# LPC4357_SDRAM.net
KiCad netlist of a schematic drawn in Altium Designer
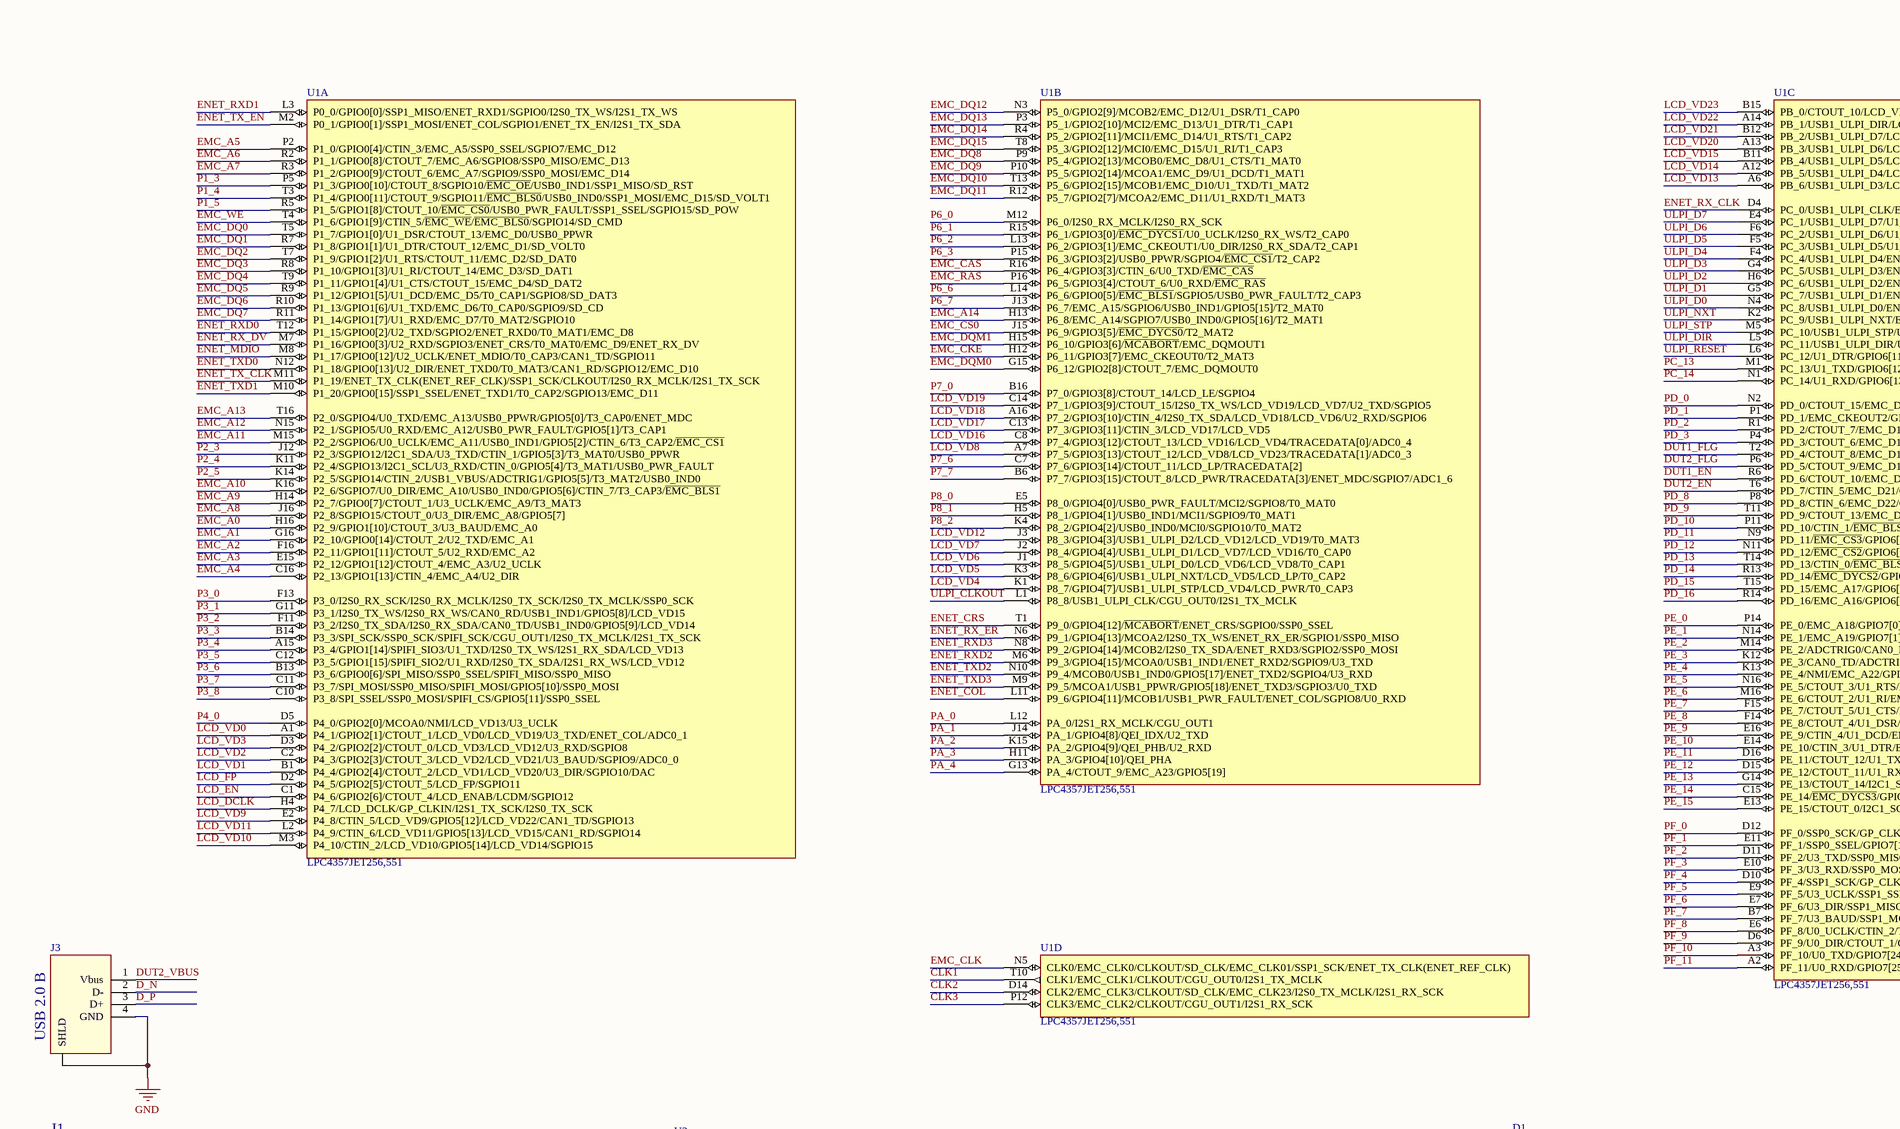
[diagram p0: LPC4357_SDRAM.SchDoc, top left]
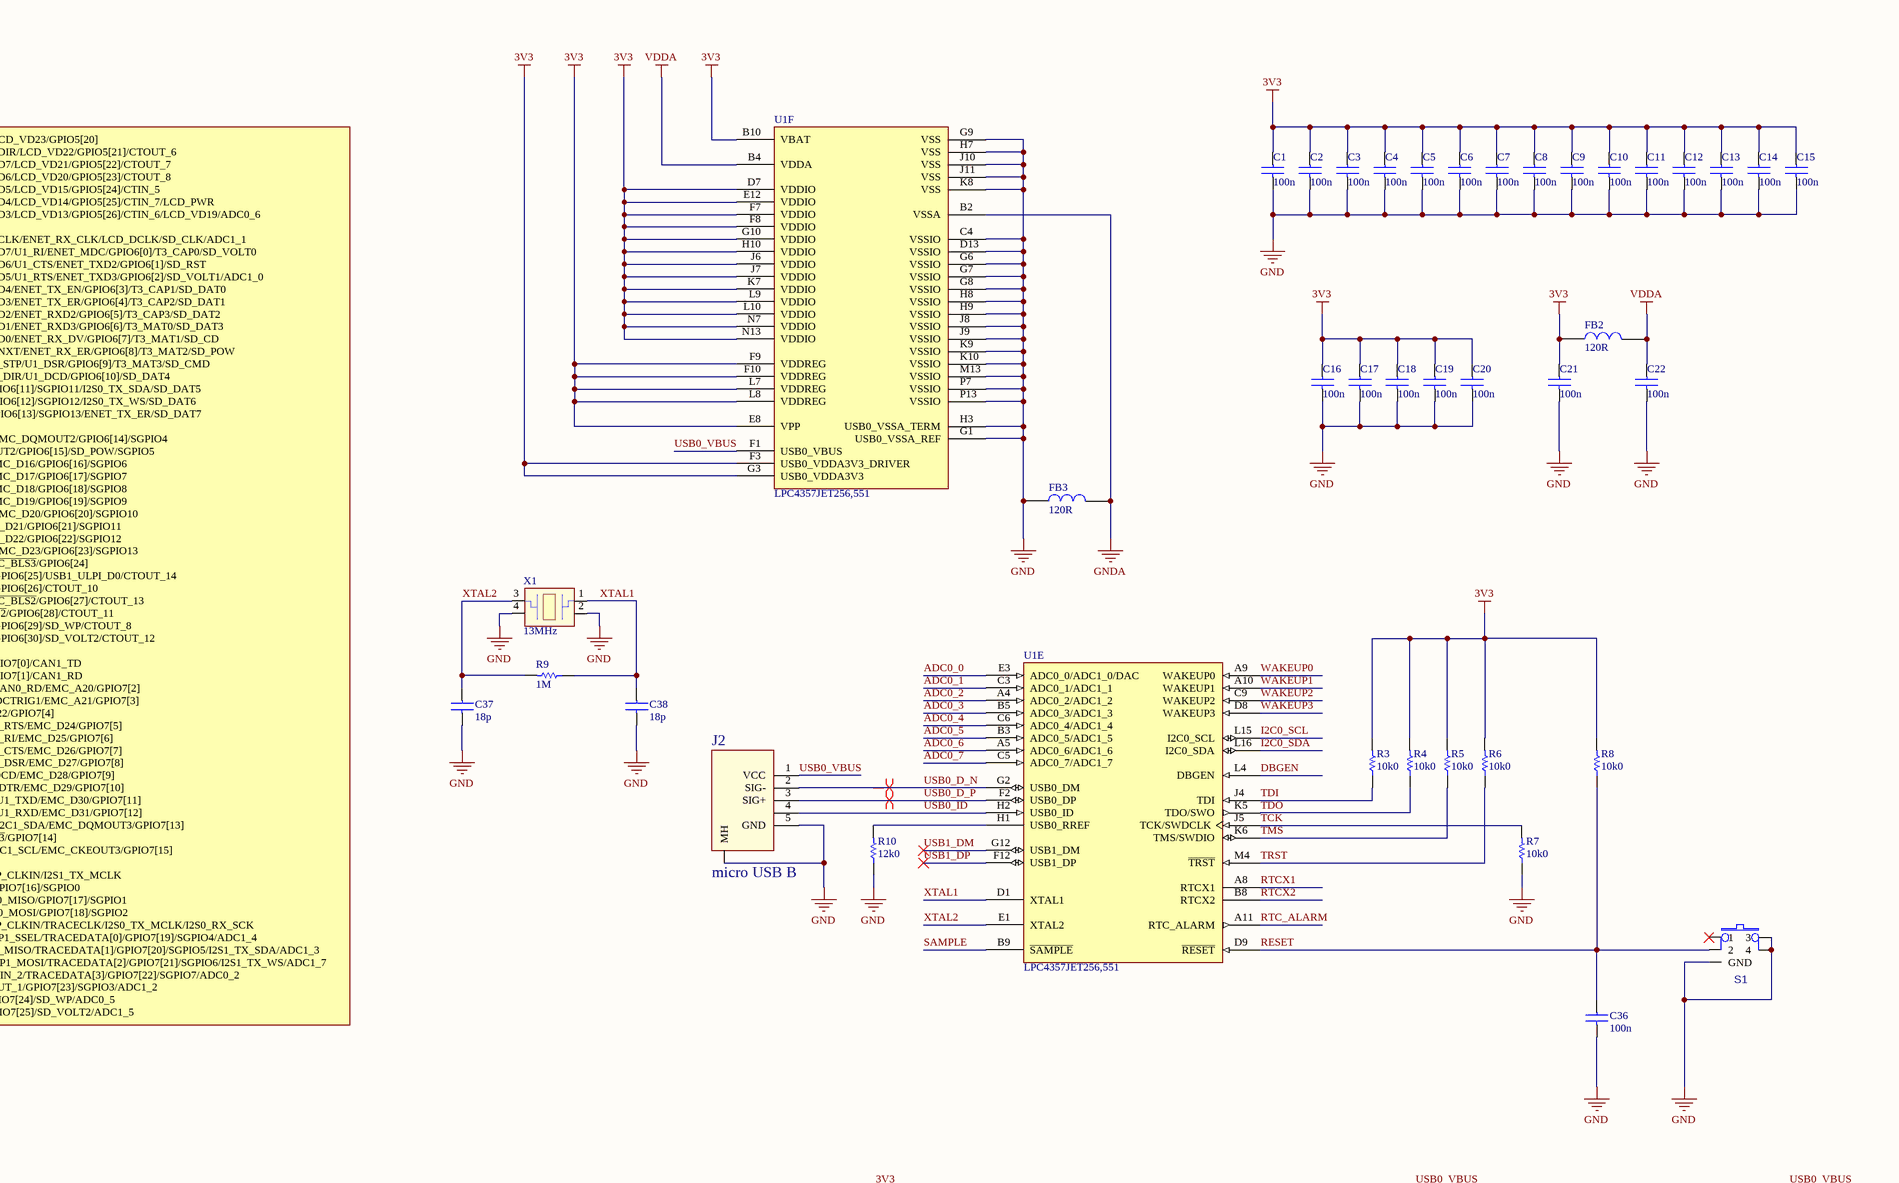
[diagram p1: LPC4357_SDRAM.SchDoc, top right]
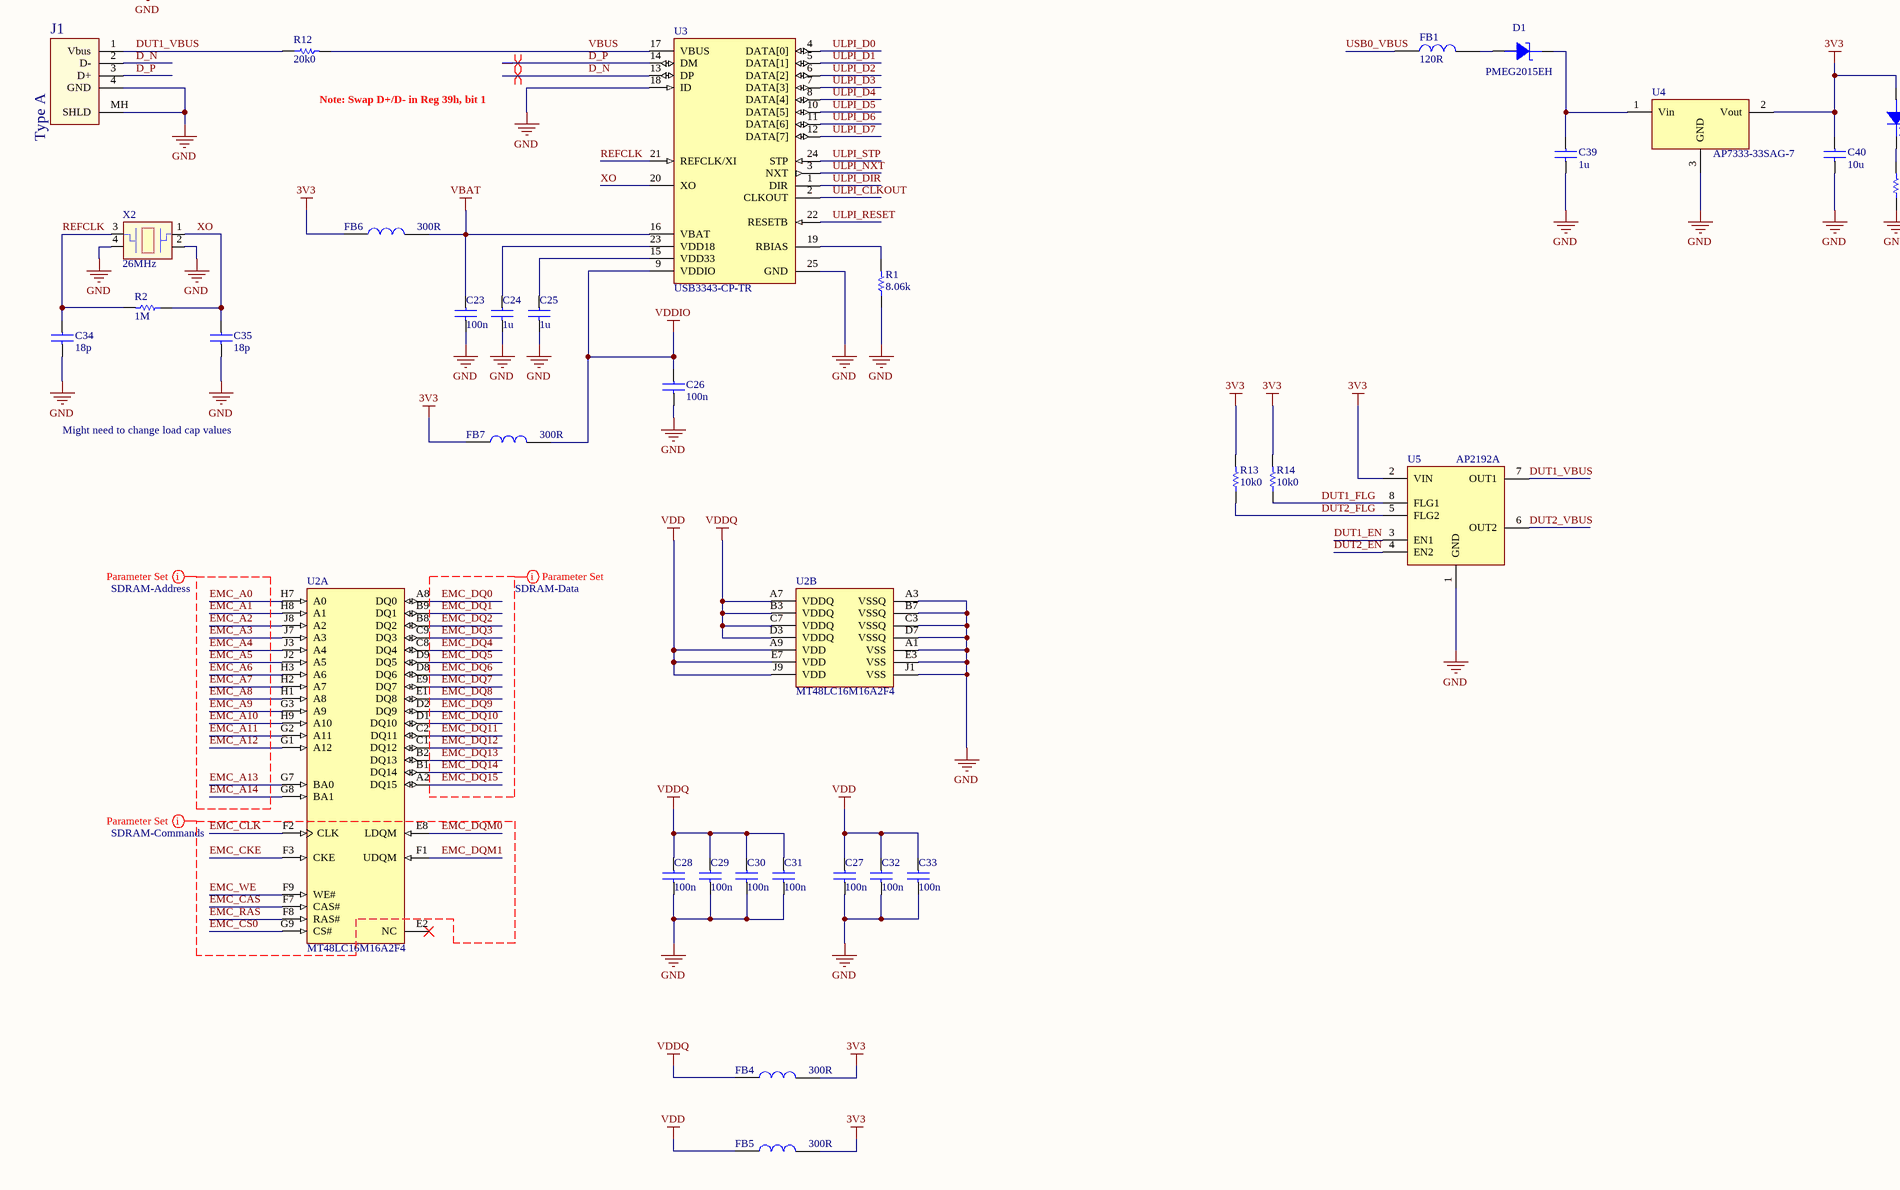
[diagram p2: LPC4357_SDRAM.SchDoc, bottom left]
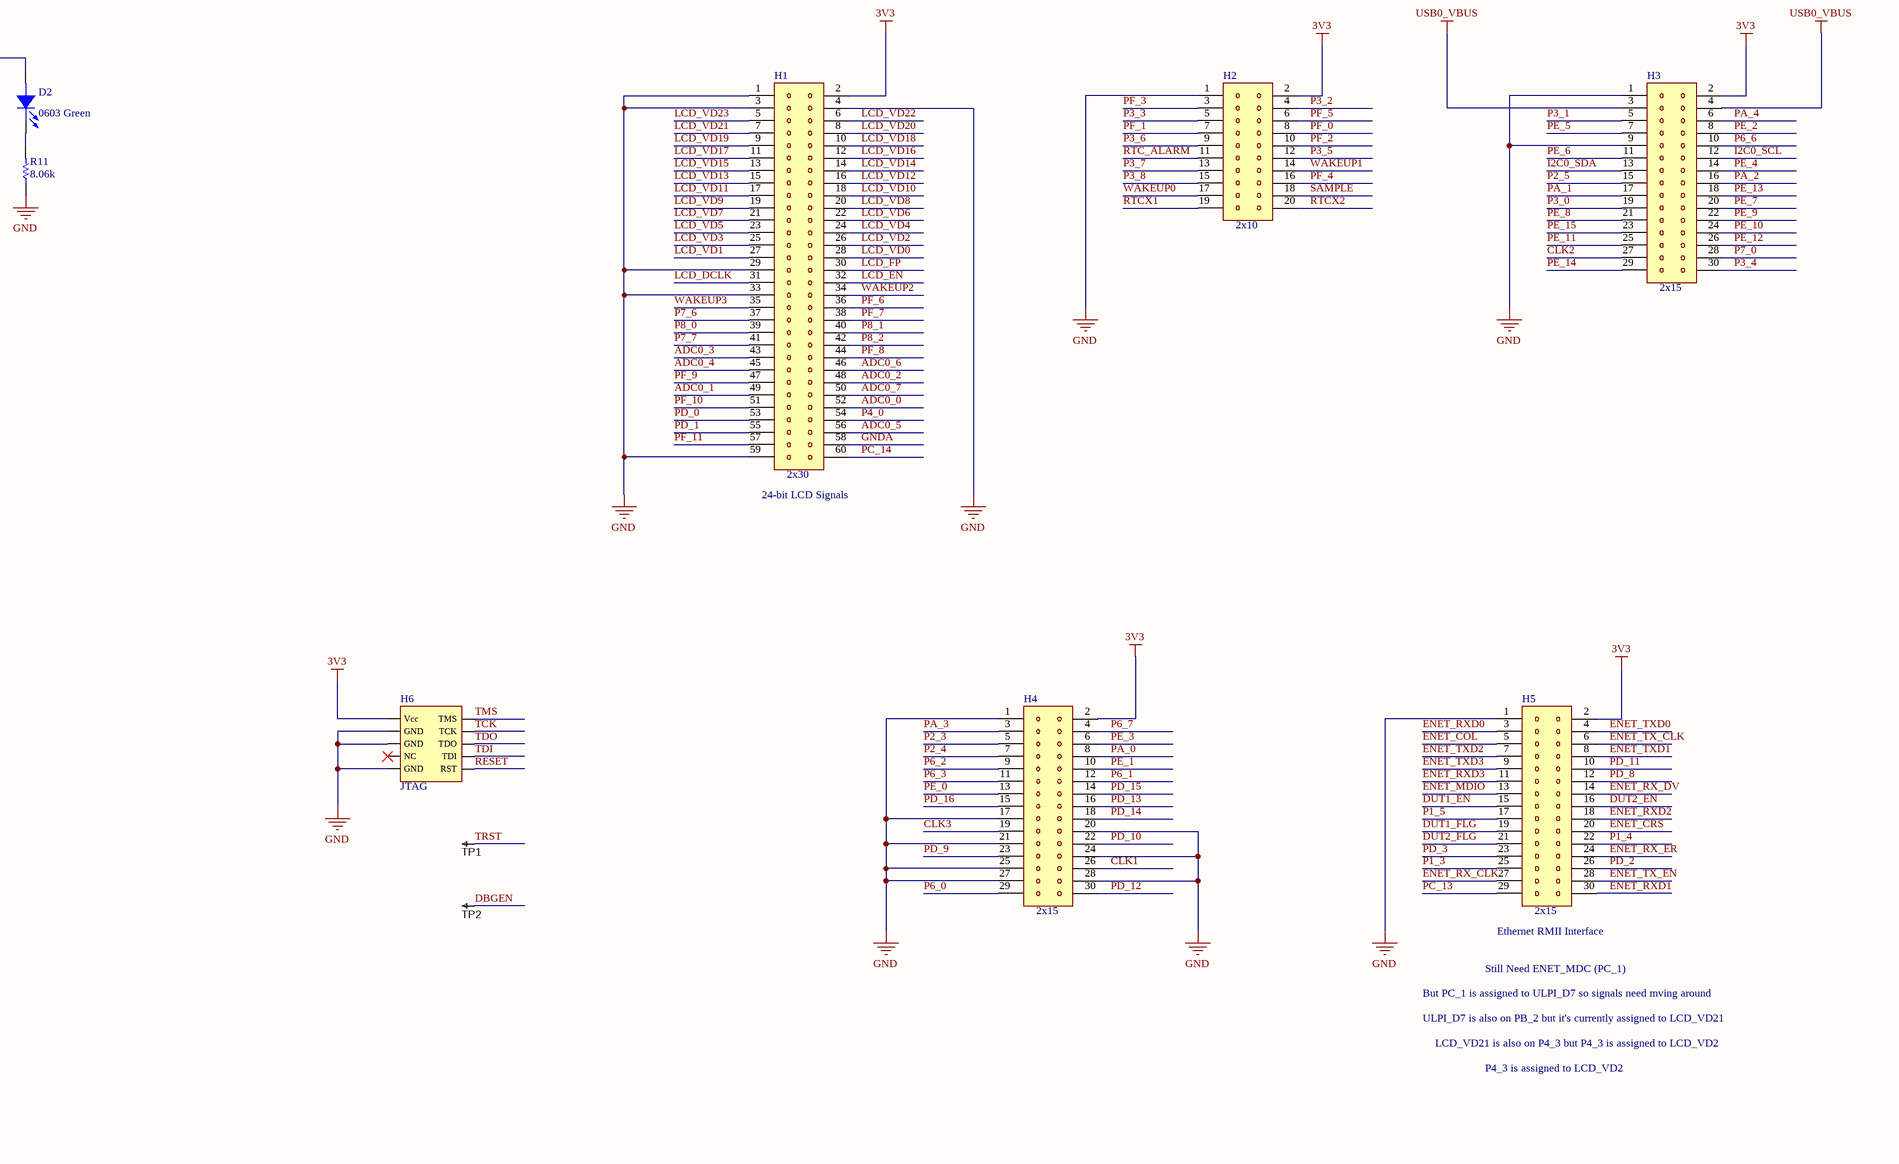
[diagram p3: LPC4357_SDRAM.SchDoc, bottom right]

(export (version "E")
  (design (tool "Eeschema 10.0.6"))
  (components
    (comp (ref "C1")
      (value "100n")
      (footprint "C_0402_N")
      (description "Cap, Chip, 100nF, 16V, +/-10%, X7R, 0402")
      (fields (field (name "MANUFACTURER") "NIC"))
      (libsource (lib "GLIB") (part "C_100n_16V_10_0402_NIC"))
    )
    (comp (ref "C2")
      (value "100n")
      (footprint "C_0402_N")
      (description "Cap, Chip, 100nF, 16V, +/-10%, X7R, 0402")
      (fields (field (name "MANUFACTURER") "NIC"))
      (libsource (lib "GLIB") (part "C_100n_16V_10_0402_NIC"))
    )
    (comp (ref "C3")
      (value "100n")
      (footprint "C_0402_N")
      (description "Cap, Chip, 100nF, 16V, +/-10%, X7R, 0402")
      (fields (field (name "MANUFACTURER") "NIC"))
      (libsource (lib "GLIB") (part "C_100n_16V_10_0402_NIC"))
    )
    (comp (ref "C4")
      (value "100n")
      (footprint "C_0402_N")
      (description "Cap, Chip, 100nF, 16V, +/-10%, X7R, 0402")
      (fields (field (name "MANUFACTURER") "NIC"))
      (libsource (lib "GLIB") (part "C_100n_16V_10_0402_NIC"))
    )
    (comp (ref "C5")
      (value "100n")
      (footprint "C_0402_N")
      (description "Cap, Chip, 100nF, 16V, +/-10%, X7R, 0402")
      (fields (field (name "MANUFACTURER") "NIC"))
      (libsource (lib "GLIB") (part "C_100n_16V_10_0402_NIC"))
    )
    (comp (ref "C6")
      (value "100n")
      (footprint "C_0402_N")
      (description "Cap, Chip, 100nF, 16V, +/-10%, X7R, 0402")
      (fields (field (name "MANUFACTURER") "NIC"))
      (libsource (lib "GLIB") (part "C_100n_16V_10_0402_NIC"))
    )
    (comp (ref "C7")
      (value "100n")
      (footprint "C_0402_N")
      (description "Cap, Chip, 100nF, 16V, +/-10%, X7R, 0402")
      (fields (field (name "MANUFACTURER") "NIC"))
      (libsource (lib "GLIB") (part "C_100n_16V_10_0402_NIC"))
    )
    (comp (ref "C8")
      (value "100n")
      (footprint "C_0402_N")
      (description "Cap, Chip, 100nF, 16V, +/-10%, X7R, 0402")
      (fields (field (name "MANUFACTURER") "NIC"))
      (libsource (lib "GLIB") (part "C_100n_16V_10_0402_NIC"))
    )
    (comp (ref "C9")
      (value "100n")
      (footprint "C_0402_N")
      (description "Cap, Chip, 100nF, 16V, +/-10%, X7R, 0402")
      (fields (field (name "MANUFACTURER") "NIC"))
      (libsource (lib "GLIB") (part "C_100n_16V_10_0402_NIC"))
    )
    (comp (ref "C10")
      (value "100n")
      (footprint "C_0402_N")
      (description "Cap, Chip, 100nF, 16V, +/-10%, X7R, 0402")
      (fields (field (name "MANUFACTURER") "NIC"))
      (libsource (lib "GLIB") (part "C_100n_16V_10_0402_NIC"))
    )
    (comp (ref "C11")
      (value "100n")
      (footprint "C_0402_N")
      (description "Cap, Chip, 100nF, 16V, +/-10%, X7R, 0402")
      (fields (field (name "MANUFACTURER") "NIC"))
      (libsource (lib "GLIB") (part "C_100n_16V_10_0402_NIC"))
    )
    (comp (ref "C12")
      (value "100n")
      (footprint "C_0402_N")
      (description "Cap, Chip, 100nF, 16V, +/-10%, X7R, 0402")
      (fields (field (name "MANUFACTURER") "NIC"))
      (libsource (lib "GLIB") (part "C_100n_16V_10_0402_NIC"))
    )
    (comp (ref "C13")
      (value "100n")
      (footprint "C_0402_N")
      (description "Cap, Chip, 100nF, 16V, +/-10%, X7R, 0402")
      (fields (field (name "MANUFACTURER") "NIC"))
      (libsource (lib "GLIB") (part "C_100n_16V_10_0402_NIC"))
    )
    (comp (ref "C14")
      (value "100n")
      (footprint "C_0402_N")
      (description "Cap, Chip, 100nF, 16V, +/-10%, X7R, 0402")
      (fields (field (name "MANUFACTURER") "NIC"))
      (libsource (lib "GLIB") (part "C_100n_16V_10_0402_NIC"))
    )
    (comp (ref "C15")
      (value "100n")
      (footprint "C_0402_N")
      (description "Cap, Chip, 100nF, 16V, +/-10%, X7R, 0402")
      (fields (field (name "MANUFACTURER") "NIC"))
      (libsource (lib "GLIB") (part "C_100n_16V_10_0402_NIC"))
    )
    (comp (ref "C16")
      (value "100n")
      (footprint "C_0402_N")
      (description "Cap, Chip, 100nF, 16V, +/-10%, X7R, 0402")
      (fields (field (name "MANUFACTURER") "NIC"))
      (libsource (lib "GLIB") (part "C_100n_16V_10_0402_NIC"))
    )
    (comp (ref "C17")
      (value "100n")
      (footprint "C_0402_N")
      (description "Cap, Chip, 100nF, 16V, +/-10%, X7R, 0402")
      (fields (field (name "MANUFACTURER") "NIC"))
      (libsource (lib "GLIB") (part "C_100n_16V_10_0402_NIC"))
    )
    (comp (ref "C18")
      (value "100n")
      (footprint "C_0402_N")
      (description "Cap, Chip, 100nF, 16V, +/-10%, X7R, 0402")
      (fields (field (name "MANUFACTURER") "NIC"))
      (libsource (lib "GLIB") (part "C_100n_16V_10_0402_NIC"))
    )
    (comp (ref "C19")
      (value "100n")
      (footprint "C_0402_N")
      (description "Cap, Chip, 100nF, 16V, +/-10%, X7R, 0402")
      (fields (field (name "MANUFACTURER") "NIC"))
      (libsource (lib "GLIB") (part "C_100n_16V_10_0402_NIC"))
    )
    (comp (ref "C20")
      (value "100n")
      (footprint "C_0402_N")
      (description "Cap, Chip, 100nF, 16V, +/-10%, X7R, 0402")
      (fields (field (name "MANUFACTURER") "NIC"))
      (libsource (lib "GLIB") (part "C_100n_16V_10_0402_NIC"))
    )
    (comp (ref "C21")
      (value "100n")
      (footprint "C_0402_N")
      (description "Cap, Chip, 100nF, 16V, +/-10%, X7R, 0402")
      (fields (field (name "MANUFACTURER") "NIC"))
      (libsource (lib "GLIB") (part "C_100n_16V_10_0402_NIC"))
    )
    (comp (ref "C22")
      (value "100n")
      (footprint "C_0402_N")
      (description "Cap, Chip, 100nF, 16V, +/-10%, X7R, 0402")
      (fields (field (name "MANUFACTURER") "NIC"))
      (libsource (lib "GLIB") (part "C_100n_16V_10_0402_NIC"))
    )
    (comp (ref "C23")
      (value "100n")
      (footprint "C_0402_N")
      (description "Cap, Chip, 100nF, 16V, +/-10%, X7R, 0402")
      (fields (field (name "MANUFACTURER") "NIC"))
      (libsource (lib "GLIB") (part "C_100n_16V_10_0402_NIC"))
    )
    (comp (ref "C24")
      (value "1u")
      (footprint "C_0402_N")
      (description "Cap, Chip, 1uF, 10V, 10%, X5R, 0402")
      (fields (field (name "MANUFACTURER") "NIC"))
      (libsource (lib "GLIB") (part "C_1u_10V_10_0402_NIC"))
    )
    (comp (ref "C25")
      (value "1u")
      (footprint "C_0402_N")
      (description "Cap, Chip, 1uF, 10V, 10%, X5R, 0402")
      (fields (field (name "MANUFACTURER") "NIC"))
      (libsource (lib "GLIB") (part "C_1u_10V_10_0402_NIC"))
    )
    (comp (ref "C26")
      (value "100n")
      (footprint "C_0402_N")
      (description "Cap, Chip, 100nF, 16V, +/-10%, X7R, 0402")
      (fields (field (name "MANUFACTURER") "NIC"))
      (libsource (lib "GLIB") (part "C_100n_16V_10_0402_NIC"))
    )
    (comp (ref "C27")
      (value "100n")
      (footprint "C_0402_N")
      (description "Cap, Chip, 100nF, 16V, +/-10%, X7R, 0402")
      (fields (field (name "MANUFACTURER") "NIC"))
      (libsource (lib "GLIB") (part "C_100n_16V_10_0402_NIC"))
    )
    (comp (ref "C28")
      (value "100n")
      (footprint "C_0402_N")
      (description "Cap, Chip, 100nF, 16V, +/-10%, X7R, 0402")
      (fields (field (name "MANUFACTURER") "NIC"))
      (libsource (lib "GLIB") (part "C_100n_16V_10_0402_NIC"))
    )
    (comp (ref "C29")
      (value "100n")
      (footprint "C_0402_N")
      (description "Cap, Chip, 100nF, 16V, +/-10%, X7R, 0402")
      (fields (field (name "MANUFACTURER") "NIC"))
      (libsource (lib "GLIB") (part "C_100n_16V_10_0402_NIC"))
    )
    (comp (ref "C30")
      (value "100n")
      (footprint "C_0402_N")
      (description "Cap, Chip, 100nF, 16V, +/-10%, X7R, 0402")
      (fields (field (name "MANUFACTURER") "NIC"))
      (libsource (lib "GLIB") (part "C_100n_16V_10_0402_NIC"))
    )
    (comp (ref "C31")
      (value "100n")
      (footprint "C_0402_N")
      (description "Cap, Chip, 100nF, 16V, +/-10%, X7R, 0402")
      (fields (field (name "MANUFACTURER") "NIC"))
      (libsource (lib "GLIB") (part "C_100n_16V_10_0402_NIC"))
    )
    (comp (ref "C32")
      (value "100n")
      (footprint "C_0402_N")
      (description "Cap, Chip, 100nF, 16V, +/-10%, X7R, 0402")
      (fields (field (name "MANUFACTURER") "NIC"))
      (libsource (lib "GLIB") (part "C_100n_16V_10_0402_NIC"))
    )
    (comp (ref "C33")
      (value "100n")
      (footprint "C_0402_N")
      (description "Cap, Chip, 100nF, 16V, +/-10%, X7R, 0402")
      (fields (field (name "MANUFACTURER") "NIC"))
      (libsource (lib "GLIB") (part "C_100n_16V_10_0402_NIC"))
    )
    (comp (ref "C34")
      (value "18p")
      (footprint "C_0402_N")
      (description "Cap, Chip, 18pF, 25V, 10%, NPO 0402")
      (fields (field (name "MANUFACTURER") "NIC"))
      (libsource (lib "GLIB") (part "C_18p_25V_10_0402_NIC"))
    )
    (comp (ref "C35")
      (value "18p")
      (footprint "C_0402_N")
      (description "Cap, Chip, 18pF, 25V, 10%, NPO 0402")
      (fields (field (name "MANUFACTURER") "NIC"))
      (libsource (lib "GLIB") (part "C_18p_25V_10_0402_NIC"))
    )
    (comp (ref "C36")
      (value "100n")
      (footprint "C_0402_N")
      (description "Cap, Chip, 100nF, 16V, +/-10%, X7R, 0402")
      (fields (field (name "MANUFACTURER") "NIC"))
      (libsource (lib "GLIB") (part "C_100n_16V_10_0402_NIC"))
    )
    (comp (ref "C37")
      (value "18p")
      (footprint "C_0402_N")
      (description "Cap, Chip, 18pF, 25V, 10%, NPO 0402")
      (fields (field (name "MANUFACTURER") "NIC"))
      (libsource (lib "GLIB") (part "C_18p_25V_10_0402_NIC"))
    )
    (comp (ref "C38")
      (value "18p")
      (footprint "C_0402_N")
      (description "Cap, Chip, 18pF, 25V, 10%, NPO 0402")
      (fields (field (name "MANUFACTURER") "NIC"))
      (libsource (lib "GLIB") (part "C_18p_25V_10_0402_NIC"))
    )
    (comp (ref "C39")
      (value "1u")
      (footprint "C_0402_N")
      (description "Cap, Chip, 1uF, 10V, 10%, X5R, 0402")
      (fields (field (name "MANUFACTURER") "NIC"))
      (libsource (lib "GLIB") (part "C_1u_10V_10_0402_NIC"))
    )
    (comp (ref "C40")
      (value "10u")
      (footprint "0603x55")
      (description "Cap, Chip, 10uF, 10V, ± 15%, X5R, 0603")
      (fields (field (name "MANUFACTURER") "NIC"))
      (libsource (lib "GLIB") (part "C_10u_10V_10_0603_NIC"))
    )
    (comp (ref "D1")
      (value "PMEG2015EH")
      (footprint "SOD123F")
      (description "Diode, Schottky Rectifier, 20V, 1.5A, SOT123F")
      (fields (field (name "VOLTAGE") "20V") (field (name "MANUFACTURER") "NXP Semiconductors"))
      (libsource (lib "GLIB") (part "D_PMEG2015EH_20V_1A5_SOT123F"))
    )
    (comp (ref "D2")
      (value "0603 Green")
      (footprint "D_0603")
      (description "0603 LED, Green")
      (fields (field (name "MANUFACTURER") "Lite-on"))
      (libsource (lib "GLIB") (part "D_LED-0603_LTST-C190KGKT"))
    )
    (comp (ref "FB1")
      (value "120R")
      (footprint "L_0603")
      (description "Ferrite bead,120 ohm@100MHz,0.30 ohm @DC, 500mA, 0603")
      (fields (field (name "MANUFACTURER") "NIC"))
      (libsource (lib "GLIB") (part "FB_120R_0603_NIC"))
    )
    (comp (ref "FB2")
      (value "120R")
      (footprint "L_0603")
      (description "Ferrite bead,120 ohm@100MHz,0.30 ohm @DC, 500mA, 0603")
      (fields (field (name "MANUFACTURER") "NIC"))
      (libsource (lib "GLIB") (part "FB_120R_0603_NIC"))
    )
    (comp (ref "FB3")
      (value "120R")
      (footprint "L_0603")
      (description "Ferrite bead,120 ohm@100MHz,0.30 ohm @DC, 500mA, 0603")
      (fields (field (name "MANUFACTURER") "NIC"))
      (libsource (lib "GLIB") (part "FB_120R_0603_NIC"))
    )
    (comp (ref "FB4")
      (value "300R")
      (footprint "FB_0402-NIC")
      (description "Ferrite bead,300 ohm@100MHz,0.15 ohm @DC, 1A, 0402")
      (fields (field (name "MANUFACTURER") "NIC"))
      (libsource (lib "GLIB") (part "FB_300R_0402_NIC"))
    )
    (comp (ref "FB5")
      (value "300R")
      (footprint "FB_0402-NIC")
      (description "Ferrite bead,300 ohm@100MHz,0.15 ohm @DC, 1A, 0402")
      (fields (field (name "MANUFACTURER") "NIC"))
      (libsource (lib "GLIB") (part "FB_300R_0402_NIC"))
    )
    (comp (ref "FB6")
      (value "300R")
      (footprint "FB_0402-NIC")
      (description "Ferrite bead,300 ohm@100MHz,0.15 ohm @DC, 1A, 0402")
      (fields (field (name "MANUFACTURER") "NIC"))
      (libsource (lib "GLIB") (part "FB_300R_0402_NIC"))
    )
    (comp (ref "FB7")
      (value "300R")
      (footprint "FB_0402-NIC")
      (description "Ferrite bead,300 ohm@100MHz,0.15 ohm @DC, 1A, 0402")
      (fields (field (name "MANUFACTURER") "NIC"))
      (libsource (lib "GLIB") (part "FB_300R_0402_NIC"))
    )
    (comp (ref "H1")
      (value "2x30")
      (footprint "HDR_2x30_1.27mm")
      (description "CONN, Header, 2x30, TH, 1.27mm")
      (fields (field (name "MANUFACTURER") "Shenzhen Cankemeng"))
      (libsource (lib "GLIB") (part "JP_2x30_1.27mm"))
    )
    (comp (ref "H2")
      (value "2x10")
      (footprint "HDR_2x10_1.27mm")
      (description "CONN, Header, 2x10, TH, 1.27mm")
      (libsource (lib "GLIB") (part "JP_2x10_1.27mm"))
    )
    (comp (ref "H3")
      (value "2x15")
      (footprint "HDR_2x15_1.27mm")
      (description "CONN, Header, 2x15, TH, 1.27mm")
      (libsource (lib "GLIB") (part "JP_2x15_1.27mm"))
    )
    (comp (ref "H4")
      (value "2x15")
      (footprint "HDR_2x15_1.27mm")
      (description "CONN, Header, 2x15, TH, 1.27mm")
      (libsource (lib "GLIB") (part "JP_2x15_1.27mm"))
    )
    (comp (ref "H5")
      (value "2x15")
      (footprint "HDR_2x15_1.27mm")
      (description "CONN, Header, 2x15, TH, 1.27mm")
      (libsource (lib "GLIB") (part "JP_2x15_1.27mm"))
    )
    (comp (ref "H6")
      (value "JTAG")
      (footprint "JTAG_FTSH-105-01-XXX-D-K")
      (description "CONN, Header 2x5, TH, 1.27mm")
      (fields (field (name "MANUFACTURER") "Samtec"))
      (libsource (lib "GLIB") (part "JP_JTAG-FTSH_1.27"))
    )
    (comp (ref "J1")
      (value "Type A")
      (footprint "USB_A_F_SIDE_REVERSE_TH")
      (description "USB, Type A, Side Insert, Revese PinoutRA")
      (fields (field (name "MANUFACTURER") "Jing Extension"))
      (libsource (lib "GLIB") (part "J_USB_A_Rotate_Reverse_TH"))
    )
    (comp (ref "J2")
      (value "micro USB B")
      (footprint "10118194")
      (description "CONN RECEPT MICRO USB RA 5POS SMD")
      (fields (field (name "MANUFACTURER") "FCI"))
      (libsource (lib "GLIB") (part "J_microUSB_B_SMD-FCI"))
    )
    (comp (ref "J3")
      (value "USB 2.0 B")
      (footprint "USB_B_F_RA_TH")
      (description "CONN RCPT USB 2.0 TYPE B R/A 4PS")
      (fields (field (name "MANUFACTURER") "FCI"))
      (libsource (lib "GLIB") (part "J_USB_B_2.0_RA"))
    )
    (comp (ref "R1")
      (value "8.06k")
      (footprint "R_0402-N")
      (description "Resistor 8.06 kOhm, 1%, 0.1W, 0402")
      (libsource (lib "GLIB") (part "Res Semi"))
    )
    (comp (ref "R2")
      (value "1M")
      (footprint "R_0402-N")
      (description "Semiconductor Resistor")
      (libsource (lib "GLIB") (part "Res Semi"))
    )
    (comp (ref "R3")
      (value "10k0")
      (footprint "R_0402-N")
      (description "Resistor, 10.0 kΩ, 1%, 0.06W, 0402")
      (fields (field (name "MANUFACTURER") "NIC"))
      (libsource (lib "GLIB") (part "R_10k0_60mW_1_0402_NIC"))
    )
    (comp (ref "R4")
      (value "10k0")
      (footprint "R_0402-N")
      (description "Resistor, 10.0 kΩ, 1%, 0.06W, 0402")
      (fields (field (name "MANUFACTURER") "NIC"))
      (libsource (lib "GLIB") (part "R_10k0_60mW_1_0402_NIC"))
    )
    (comp (ref "R5")
      (value "10k0")
      (footprint "R_0402-N")
      (description "Resistor, 10.0 kΩ, 1%, 0.06W, 0402")
      (fields (field (name "MANUFACTURER") "NIC"))
      (libsource (lib "GLIB") (part "R_10k0_60mW_1_0402_NIC"))
    )
    (comp (ref "R6")
      (value "10k0")
      (footprint "R_0402-N")
      (description "Resistor, 10.0 kΩ, 1%, 0.06W, 0402")
      (fields (field (name "MANUFACTURER") "NIC"))
      (libsource (lib "GLIB") (part "R_10k0_60mW_1_0402_NIC"))
    )
    (comp (ref "R7")
      (value "10k0")
      (footprint "R_0402-N")
      (description "Resistor, 10.0 kΩ, 1%, 0.06W, 0402")
      (fields (field (name "MANUFACTURER") "NIC"))
      (libsource (lib "GLIB") (part "R_10k0_60mW_1_0402_NIC"))
    )
    (comp (ref "R8")
      (value "10k0")
      (footprint "R_0402-N")
      (description "Resistor, 10.0 kΩ, 1%, 0.06W, 0402")
      (fields (field (name "MANUFACTURER") "NIC"))
      (libsource (lib "GLIB") (part "R_10k0_60mW_1_0402_NIC"))
    )
    (comp (ref "R9")
      (value "1M")
      (footprint "R_0402-N")
      (description "Semiconductor Resistor")
      (libsource (lib "GLIB") (part "Res Semi"))
    )
    (comp (ref "R10")
      (value "12k0")
      (footprint "R_0402-N")
      (description "Resistor 12.0 kΩ, 1%, 0.06W, 0402")
      (fields (field (name "MANUFACTURER") "NIC"))
      (libsource (lib "GLIB") (part "R_12k0_60mW_1_0402_NIC"))
    )
    (comp (ref "R11")
      (value "8.06k")
      (footprint "R_0402-N")
      (description "Resistor 8.06 kOhm, 1%, 0.1W, 0402")
      (libsource (lib "GLIB") (part "Res Semi"))
    )
    (comp (ref "R12")
      (value "20k0")
      (footprint "R_0402-N")
      (description "Resistor 20 kOhm, 1%, 0.1W, 0603")
      (fields (field (name "MANUFACTURER") "NIC"))
      (libsource (lib "GLIB") (part "R_20k0_100mW_1_0603_NIC"))
    )
    (comp (ref "R13")
      (value "10k0")
      (footprint "R_0402-N")
      (description "Resistor, 10.0 kΩ, 1%, 0.06W, 0402")
      (fields (field (name "MANUFACTURER") "NIC"))
      (libsource (lib "GLIB") (part "R_10k0_60mW_1_0402_NIC"))
    )
    (comp (ref "R14")
      (value "10k0")
      (footprint "R_0402-N")
      (description "Resistor, 10.0 kΩ, 1%, 0.06W, 0402")
      (fields (field (name "MANUFACTURER") "NIC"))
      (libsource (lib "GLIB") (part "R_10k0_60mW_1_0402_NIC"))
    )
    (comp (ref "S1")
      (value "PTS840")
      (footprint "SW_PTS840")
      (description "SWITCH SPST RA, 50mA, 24V, SMT")
      (fields (field (name "MANUFACTURER") "C&K"))
      (libsource (lib "GLIB") (part "SW_PTS840_RA_SMT"))
    )
    (comp (ref "TP1")
      (value "TP_60mil-pad")
      (footprint "TP-R50")
      (description "SMD test pin")
      (libsource (lib "GLIB") (part "TP_50mil-pad"))
    )
    (comp (ref "TP2")
      (value "TP_60mil-pad")
      (footprint "TP-R50")
      (description "SMD test pin")
      (libsource (lib "GLIB") (part "TP_50mil-pad"))
    )
    (comp (ref "U1")
      (value "LPC4357JET256,551")
      (footprint "NXP-SOT740-2")
      (fields (field (name "MANUFACTURER") "NXP Semiconductors") (field (name "PARTNUMBER") "LPC4357JET256"))
      (libsource (lib "GLIB") (part "U_LPC4357JET256_BGA256"))
    )
    (comp (ref "U2")
      (value "MT48LC16M16A2F4")
      (footprint "VFBGA54_8x8")
      (description "256Mb PC133 SDR SDRAM, 16Mb x 16, 7.5ns, 3.3V, 0 to 70 degC, 54-Ball VFBGA, Pb-Free")
      (fields (field (name "PARTNUMBER") "MT48LC16M16A2BG-75") (field (name "VOLTAGE") "3.3V"))
      (libsource (lib "GLIB") (part "U_MT48LC16M16A2F4_VFBGA54"))
    )
    (comp (ref "U3")
      (value "USB3343-CP-TR")
      (footprint "MCHP-QFN-24_A_V")
      (fields (field (name "MANUFACTURER") "Microchip"))
      (libsource (lib "GLIB") (part "U_USB3343_QFN24"))
    )
    (comp (ref "U4")
      (value "AP7333-33SAG-7")
      (footprint "SOT23_N")
      (description "IC, CONV DC/DC LDO 3.3V, 300mA, SOT23-3")
      (fields (field (name "MANUFACTURER") "STMicroelectronics"))
      (libsource (lib "GLIB") (part "U_AP7333-33SAG-7_SOT23-3"))
    )
    (comp (ref "U5")
      (value "AP2192A")
      (footprint "soic_8")
      (description "IC, USB Dual Switch w/ 1.5A Current Limit, SOIC-8")
      (fields (field (name "MANUFACTURER") "Diodes Inc"))
      (libsource (lib "GLIB") (part "U_AP2192A_SOIC8"))
    )
    (comp (ref "X1")
      (value "13MHz")
      (description "X-tal, 13.000MHz, Cl=20pF, +-18ppm, 3225")
      (fields (field (name "MANUFACTURER") "ABRACON Co"))
      (libsource (lib "GLIB") (part "X_13.000MHZ_18pF_3225"))
    )
    (comp (ref "X2")
      (value "26MHz")
      (description "X-tal, 26.000MHz, Cl=6pF, +-18ppm, 2.0 x 1.6mm")
      (fields (field (name "MANUFACTURER") "muRata"))
      (libsource (lib "GLIB") (part "X_26.000MHZ_6pF_2016"))
    )
  )
  (nets
    (net (code "1") (name "/ADC0_0") (class "Default")
      (node (ref "H1") (pin "52") (pinfunction "52_52") (pintype "passive"))
      (node (ref "U1") (pin "E3") (pinfunction "ADC0_0/ADC1_0/DAC_E3") (pintype "input"))
    )
    (net (code "2") (name "/ADC0_1") (class "Default")
      (node (ref "H1") (pin "49") (pinfunction "49_49") (pintype "passive"))
      (node (ref "U1") (pin "C3") (pinfunction "ADC0_1/ADC1_1_C3") (pintype "input"))
    )
    (net (code "3") (name "/ADC0_2") (class "Default")
      (node (ref "H1") (pin "48") (pinfunction "48_48") (pintype "passive"))
      (node (ref "U1") (pin "A4") (pinfunction "ADC0_2/ADC1_2_A4") (pintype "input"))
    )
    (net (code "4") (name "/ADC0_3") (class "Default")
      (node (ref "H1") (pin "43") (pinfunction "43_43") (pintype "passive"))
      (node (ref "U1") (pin "B5") (pinfunction "ADC0_3/ADC1_3_B5") (pintype "input"))
    )
    (net (code "5") (name "/ADC0_4") (class "Default")
      (node (ref "H1") (pin "45") (pinfunction "45_45") (pintype "passive"))
      (node (ref "U1") (pin "C6") (pinfunction "ADC0_4/ADC1_4_C6") (pintype "input"))
    )
    (net (code "6") (name "/ADC0_5") (class "Default")
      (node (ref "H1") (pin "56") (pinfunction "56_56") (pintype "passive"))
      (node (ref "U1") (pin "B3") (pinfunction "ADC0_5/ADC1_5_B3") (pintype "input"))
    )
    (net (code "7") (name "/ADC0_6") (class "Default")
      (node (ref "H1") (pin "46") (pinfunction "46_46") (pintype "passive"))
      (node (ref "U1") (pin "A5") (pinfunction "ADC0_6/ADC1_6_A5") (pintype "input"))
    )
    (net (code "8") (name "/ADC0_7") (class "Default")
      (node (ref "H1") (pin "50") (pinfunction "50_50") (pintype "passive"))
      (node (ref "U1") (pin "C5") (pinfunction "ADC0_7/ADC1_7_C5") (pintype "input"))
    )
    (net (code "9") (name "/CLK1") (class "Default")
      (node (ref "H4") (pin "26") (pinfunction "26_26") (pintype "passive"))
      (node (ref "U1") (pin "T10") (pinfunction "CLK1/EMC_CLK1/CLKOUT/CGU_OUT0/I2S1_TX_MCLK_T10") (pintype "output"))
    )
    (net (code "10") (name "/CLK2") (class "Default")
      (node (ref "H3") (pin "27") (pinfunction "27_27") (pintype "passive"))
      (node (ref "U1") (pin "D14") (pinfunction "CLK2/EMC_CLK3/CLKOUT/SD_CLK/EMC_CLK23/I2S0_TX_MCLK/I2S1_RX_SCK_D14") (pintype "bidirectional"))
    )
    (net (code "11") (name "/CLK3") (class "Default")
      (node (ref "H4") (pin "19") (pinfunction "19_19") (pintype "passive"))
      (node (ref "U1") (pin "P12") (pinfunction "CLK3/EMC_CLK2/CLKOUT/CGU_OUT1/I2S1_RX_SCK_P12") (pintype "bidirectional"))
    )
    (net (code "12") (name "/DBGEN") (class "Default")
      (node (ref "TP2") (pin "1") (pintype "passive"))
      (node (ref "U1") (pin "L4") (pinfunction "DBGEN_L4") (pintype "input"))
    )
    (net (code "13") (name "/DUT1_EN") (class "Default")
      (node (ref "H5") (pin "15") (pinfunction "15_15") (pintype "passive"))
      (node (ref "U1") (pin "R6") (pinfunction "PD_6/CTOUT_10/EMC_D20/GPIO6[20]/SGPIO10_R6") (pintype "bidirectional"))
      (node (ref "U5") (pin "3") (pinfunction "EN1_3") (pintype "passive"))
    )
    (net (code "14") (name "/DUT1_FLG") (class "Default")
      (node (ref "H5") (pin "19") (pinfunction "19_19") (pintype "passive"))
      (node (ref "R14") (pin "1") (pinfunction "1_1") (pintype "passive"))
      (node (ref "U1") (pin "T2") (pinfunction "PD_4/CTOUT_8/EMC_D18/GPIO6[18]/SGPIO8_T2") (pintype "bidirectional"))
      (node (ref "U5") (pin "8") (pinfunction "FLG1_8") (pintype "passive"))
    )
    (net (code "15") (name "/DUT1_VBUS") (class "Default")
      (node (ref "J1") (pin "1") (pinfunction "Vbus_1") (pintype "power_in"))
      (node (ref "R12") (pin "1") (pinfunction "1_1") (pintype "passive"))
      (node (ref "U5") (pin "7") (pinfunction "OUT1_7") (pintype "power_in"))
    )
    (net (code "16") (name "/DUT2_EN") (class "Default")
      (node (ref "H5") (pin "16") (pinfunction "16_16") (pintype "passive"))
      (node (ref "U1") (pin "T6") (pinfunction "PD_7/CTIN_5/EMC_D21/GPIO6[21]/SGPIO11_T6") (pintype "bidirectional"))
      (node (ref "U5") (pin "4") (pinfunction "EN2_4") (pintype "passive"))
    )
    (net (code "17") (name "/DUT2_FLG") (class "Default")
      (node (ref "H5") (pin "21") (pinfunction "21_21") (pintype "passive"))
      (node (ref "R13") (pin "1") (pinfunction "1_1") (pintype "passive"))
      (node (ref "U1") (pin "P6") (pinfunction "PD_5/CTOUT_9/EMC_D19/GPIO6[19]/SGPIO9_P6") (pintype "bidirectional"))
      (node (ref "U5") (pin "5") (pinfunction "FLG2_5") (pintype "passive"))
    )
    (net (code "18") (name "/DUT2_VBUS") (class "Default")
      (node (ref "J3") (pin "1") (pinfunction "Vbus_1") (pintype "passive"))
      (node (ref "U5") (pin "6") (pinfunction "OUT2_6") (pintype "power_in"))
    )
    (net (code "19") (name "/D_N") (class "Default")
      (node (ref "J1") (pin "2") (pinfunction "D-_2") (pintype "passive"))
      (node (ref "J3") (pin "2") (pinfunction "D-_2") (pintype "passive"))
      (node (ref "U3") (pin "13") (pinfunction "DP_13") (pintype "bidirectional"))
    )
    (net (code "20") (name "/D_P") (class "Default")
      (node (ref "J1") (pin "3") (pinfunction "D+_3") (pintype "passive"))
      (node (ref "J3") (pin "3") (pinfunction "D+_3") (pintype "passive"))
      (node (ref "U3") (pin "14") (pinfunction "DM_14") (pintype "bidirectional"))
    )
    (net (code "21") (name "/EMC_A0") (class "Default")
      (node (ref "U1") (pin "H16") (pinfunction "P2_9/GPIO1[10]/CTOUT_3/U3_BAUD/EMC_A0_H16") (pintype "bidirectional"))
      (node (ref "U2") (pin "H7") (pinfunction "A0_H7") (pintype "input"))
    )
    (net (code "22") (name "/EMC_A1") (class "Default")
      (node (ref "U1") (pin "G16") (pinfunction "P2_10/GPIO0[14]/CTOUT_2/U2_TXD/EMC_A1_G16") (pintype "bidirectional"))
      (node (ref "U2") (pin "H8") (pinfunction "A1_H8") (pintype "input"))
    )
    (net (code "23") (name "/EMC_A2") (class "Default")
      (node (ref "U1") (pin "F16") (pinfunction "P2_11/GPIO1[11]/CTOUT_5/U2_RXD/EMC_A2_F16") (pintype "bidirectional"))
      (node (ref "U2") (pin "J8") (pinfunction "A2_J8") (pintype "input"))
    )
    (net (code "24") (name "/EMC_A3") (class "Default")
      (node (ref "U1") (pin "E15") (pinfunction "P2_12/GPIO1[12]/CTOUT_4/EMC_A3/U2_UCLK_E15") (pintype "bidirectional"))
      (node (ref "U2") (pin "J7") (pinfunction "A3_J7") (pintype "input"))
    )
    (net (code "25") (name "/EMC_A4") (class "Default")
      (node (ref "U1") (pin "C16") (pinfunction "P2_13/GPIO1[13]/CTIN_4/EMC_A4/U2_DIR_C16") (pintype "bidirectional"))
      (node (ref "U2") (pin "J3") (pinfunction "A4_J3") (pintype "input"))
    )
    (net (code "26") (name "/EMC_A5") (class "Default")
      (node (ref "U1") (pin "P2") (pinfunction "P1_0/GPIO0[4]/CTIN_3/EMC_A5/SSP0_SSEL/SGPIO7/EMC_D12_P2") (pintype "bidirectional"))
      (node (ref "U2") (pin "J2") (pinfunction "A5_J2") (pintype "input"))
    )
    (net (code "27") (name "/EMC_A6") (class "Default")
      (node (ref "U1") (pin "R2") (pinfunction "P1_1/GPIO0[8]/CTOUT_7/EMC_A6/SGPIO8/SSP0_MISO/EMC_D13_R2") (pintype "bidirectional"))
      (node (ref "U2") (pin "H3") (pinfunction "A6_H3") (pintype "input"))
    )
    (net (code "28") (name "/EMC_A7") (class "Default")
      (node (ref "U1") (pin "R3") (pinfunction "P1_2/GPIO0[9]/CTOUT_6/EMC_A7/SGPIO9/SSP0_MOSI/EMC_D14_R3") (pintype "bidirectional"))
      (node (ref "U2") (pin "H2") (pinfunction "A7_H2") (pintype "input"))
    )
    (net (code "29") (name "/EMC_A8") (class "Default")
      (node (ref "U1") (pin "J16") (pinfunction "P2_8/SGPIO15/CTOUT_0/U3_DIR/EMC_A8/GPIO5[7]_J16") (pintype "bidirectional"))
      (node (ref "U2") (pin "H1") (pinfunction "A8_H1") (pintype "input"))
    )
    (net (code "30") (name "/EMC_A9") (class "Default")
      (node (ref "U1") (pin "H14") (pinfunction "P2_7/GPIO0[7]/CTOUT_1/U3_UCLK/EMC_A9/T3_MAT3_H14") (pintype "bidirectional"))
      (node (ref "U2") (pin "G3") (pinfunction "A9_G3") (pintype "input"))
    )
    (net (code "31") (name "/EMC_A10") (class "Default")
      (node (ref "U1") (pin "K16") (pinfunction "P2_6/SGPIO7/U0_DIR/EMC_A10/USB0_IND0/GPIO5[6]/CTIN_7/T3_CAP3/~{EMC_BLS1}_K16") (pintype "bidirectional"))
      (node (ref "U2") (pin "H9") (pinfunction "A10_H9") (pintype "input"))
    )
    (net (code "32") (name "/EMC_A11") (class "Default")
      (node (ref "U1") (pin "M15") (pinfunction "P2_2/SGPIO6/U0_UCLK/EMC_A11/USB0_IND1/GPIO5[2]/CTIN_6/T3_CAP2/~{EMC_CS1}_M15") (pintype "bidirectional"))
      (node (ref "U2") (pin "G2") (pinfunction "A11_G2") (pintype "input"))
    )
    (net (code "33") (name "/EMC_A12") (class "Default")
      (node (ref "U1") (pin "N15") (pinfunction "P2_1/SGPIO5/U0_RXD/EMC_A12/USB0_PWR_FAULT/GPIO5[1]/T3_CAP1_N15") (pintype "bidirectional"))
      (node (ref "U2") (pin "G1") (pinfunction "A12_G1") (pintype "input"))
    )
    (net (code "34") (name "/EMC_A13") (class "Default")
      (node (ref "U1") (pin "T16") (pinfunction "P2_0/SGPIO4/U0_TXD/EMC_A13/USB0_PPWR/GPIO5[0]/T3_CAP0/ENET_MDC_T16") (pintype "bidirectional"))
      (node (ref "U2") (pin "G7") (pinfunction "BA0_G7") (pintype "input"))
    )
    (net (code "35") (name "/EMC_A14") (class "Default")
      (node (ref "U1") (pin "H13") (pinfunction "P6_8/EMC_A14/SGPIO7/USB0_IND0/GPIO5[16]/T2_MAT1_H13") (pintype "bidirectional"))
      (node (ref "U2") (pin "G8") (pinfunction "BA1_G8") (pintype "input"))
    )
    (net (code "36") (name "/EMC_CAS") (class "Default")
      (node (ref "U1") (pin "R16") (pinfunction "P6_4/GPIO3[3]/CTIN_6/U0_TXD/~{EMC_CAS}_R16") (pintype "bidirectional"))
      (node (ref "U2") (pin "F7") (pinfunction "CAS#_F7") (pintype "input"))
    )
    (net (code "37") (name "/EMC_CKE") (class "Default")
      (node (ref "U1") (pin "H12") (pinfunction "P6_11/GPIO3[7]/EMC_CKEOUT0/T2_MAT3_H12") (pintype "bidirectional"))
      (node (ref "U2") (pin "F3") (pinfunction "CKE_F3") (pintype "input"))
    )
    (net (code "38") (name "/EMC_CLK") (class "Default")
      (node (ref "U1") (pin "N5") (pinfunction "CLK0/EMC_CLK0/CLKOUT/SD_CLK/EMC_CLK01/SSP1_SCK/ENET_TX_CLK(ENET_REF_CLK)_N5") (pintype "bidirectional"))
      (node (ref "U2") (pin "F2") (pinfunction "CLK_F2") (pintype "input"))
    )
    (net (code "39") (name "/EMC_CS0") (class "Default")
      (node (ref "U1") (pin "J15") (pinfunction "P6_9/GPIO3[5]/~{EMC_DYCS0}/T2_MAT2_J15") (pintype "bidirectional"))
      (node (ref "U2") (pin "G9") (pinfunction "CS#_G9") (pintype "input"))
    )
    (net (code "40") (name "/EMC_DQ0") (class "Default")
      (node (ref "U1") (pin "T5") (pinfunction "P1_7/GPIO1[0]/U1_DSR/CTOUT_13/EMC_D0/USB0_PPWR_T5") (pintype "bidirectional"))
      (node (ref "U2") (pin "A8") (pinfunction "DQ0_A8") (pintype "bidirectional"))
    )
    (net (code "41") (name "/EMC_DQ1") (class "Default")
      (node (ref "U1") (pin "R7") (pinfunction "P1_8/GPIO1[1]/U1_DTR/CTOUT_12/EMC_D1/SD_VOLT0_R7") (pintype "bidirectional"))
      (node (ref "U2") (pin "B9") (pinfunction "DQ1_B9") (pintype "bidirectional"))
    )
    (net (code "42") (name "/EMC_DQ2") (class "Default")
      (node (ref "U1") (pin "T7") (pinfunction "P1_9/GPIO1[2]/U1_RTS/CTOUT_11/EMC_D2/SD_DAT0_T7") (pintype "bidirectional"))
      (node (ref "U2") (pin "B8") (pinfunction "DQ2_B8") (pintype "bidirectional"))
    )
    (net (code "43") (name "/EMC_DQ3") (class "Default")
      (node (ref "U1") (pin "R8") (pinfunction "P1_10/GPIO1[3]/U1_RI/CTOUT_14/EMC_D3/SD_DAT1_R8") (pintype "bidirectional"))
      (node (ref "U2") (pin "C9") (pinfunction "DQ3_C9") (pintype "bidirectional"))
    )
    (net (code "44") (name "/EMC_DQ4") (class "Default")
      (node (ref "U1") (pin "T9") (pinfunction "P1_11/GPIO1[4]/U1_CTS/CTOUT_15/EMC_D4/SD_DAT2_T9") (pintype "bidirectional"))
      (node (ref "U2") (pin "C8") (pinfunction "DQ4_C8") (pintype "bidirectional"))
    )
    (net (code "45") (name "/EMC_DQ5") (class "Default")
      (node (ref "U1") (pin "R9") (pinfunction "P1_12/GPIO1[5]/U1_DCD/EMC_D5/T0_CAP1/SGPIO8/SD_DAT3_R9") (pintype "bidirectional"))
      (node (ref "U2") (pin "D9") (pinfunction "DQ5_D9") (pintype "bidirectional"))
    )
    (net (code "46") (name "/EMC_DQ6") (class "Default")
      (node (ref "U1") (pin "R10") (pinfunction "P1_13/GPIO1[6]/U1_TXD/EMC_D6/T0_CAP0/SGPIO9/SD_CD_R10") (pintype "bidirectional"))
      (node (ref "U2") (pin "D8") (pinfunction "DQ6_D8") (pintype "bidirectional"))
    )
    (net (code "47") (name "/EMC_DQ7") (class "Default")
      (node (ref "U1") (pin "R11") (pinfunction "P1_14/GPIO1[7]/U1_RXD/EMC_D7/T0_MAT2/SGPIO10_R11") (pintype "bidirectional"))
      (node (ref "U2") (pin "E9") (pinfunction "DQ7_E9") (pintype "bidirectional"))
    )
    (net (code "48") (name "/EMC_DQ8") (class "Default")
      (node (ref "U1") (pin "P9") (pinfunction "P5_4/GPIO2[13]/MCOB0/EMC_D8/U1_CTS/T1_MAT0_P9") (pintype "bidirectional"))
      (node (ref "U2") (pin "E1") (pinfunction "DQ8_E1") (pintype "bidirectional"))
    )
    (net (code "49") (name "/EMC_DQ9") (class "Default")
      (node (ref "U1") (pin "P10") (pinfunction "P5_5/GPIO2[14]/MCOA1/EMC_D9/U1_DCD/T1_MAT1_P10") (pintype "bidirectional"))
      (node (ref "U2") (pin "D2") (pinfunction "DQ9_D2") (pintype "bidirectional"))
    )
    (net (code "50") (name "/EMC_DQ10") (class "Default")
      (node (ref "U1") (pin "T13") (pinfunction "P5_6/GPIO2[15]/MCOB1/EMC_D10/U1_TXD/T1_MAT2_T13") (pintype "bidirectional"))
      (node (ref "U2") (pin "D1") (pinfunction "DQ10_D1") (pintype "bidirectional"))
    )
    (net (code "51") (name "/EMC_DQ11") (class "Default")
      (node (ref "U1") (pin "R12") (pinfunction "P5_7/GPIO2[7]/MCOA2/EMC_D11/U1_RXD/T1_MAT3_R12") (pintype "bidirectional"))
      (node (ref "U2") (pin "C2") (pinfunction "DQ11_C2") (pintype "bidirectional"))
    )
    (net (code "52") (name "/EMC_DQ12") (class "Default")
      (node (ref "U1") (pin "N3") (pinfunction "P5_0/GPIO2[9]/MCOB2/EMC_D12/U1_DSR/T1_CAP0_N3") (pintype "bidirectional"))
      (node (ref "U2") (pin "C1") (pinfunction "DQ12_C1") (pintype "bidirectional"))
    )
    (net (code "53") (name "/EMC_DQ13") (class "Default")
      (node (ref "U1") (pin "P3") (pinfunction "P5_1/GPIO2[10]/MCI2/EMC_D13/U1_DTR/T1_CAP1_P3") (pintype "bidirectional"))
      (node (ref "U2") (pin "B2") (pinfunction "DQ13_B2") (pintype "bidirectional"))
    )
    (net (code "54") (name "/EMC_DQ14") (class "Default")
      (node (ref "U1") (pin "R4") (pinfunction "P5_2/GPIO2[11]/MCI1/EMC_D14/U1_RTS/T1_CAP2_R4") (pintype "bidirectional"))
      (node (ref "U2") (pin "B1") (pinfunction "DQ14_B1") (pintype "bidirectional"))
    )
    (net (code "55") (name "/EMC_DQ15") (class "Default")
      (node (ref "U1") (pin "T8") (pinfunction "P5_3/GPIO2[12]/MCI0/EMC_D15/U1_RI/T1_CAP3_T8") (pintype "bidirectional"))
      (node (ref "U2") (pin "A2") (pinfunction "DQ15_A2") (pintype "bidirectional"))
    )
    (net (code "56") (name "/EMC_DQM0") (class "Default")
      (node (ref "U1") (pin "G15") (pinfunction "P6_12/GPIO2[8]/CTOUT_7/EMC_DQMOUT0_G15") (pintype "bidirectional"))
      (node (ref "U2") (pin "E8") (pinfunction "LDQM_E8") (pintype "input"))
    )
    (net (code "57") (name "/EMC_DQM1") (class "Default")
      (node (ref "U1") (pin "H15") (pinfunction "P6_10/GPIO3[6]/~{MCABORT}/EMC_DQMOUT1_H15") (pintype "bidirectional"))
      (node (ref "U2") (pin "F1") (pinfunction "UDQM_F1") (pintype "input"))
    )
    (net (code "58") (name "/EMC_RAS") (class "Default")
      (node (ref "U1") (pin "P16") (pinfunction "P6_5/GPIO3[4]/CTOUT_6/U0_RXD/~{EMC_RAS}_P16") (pintype "bidirectional"))
      (node (ref "U2") (pin "F8") (pinfunction "RAS#_F8") (pintype "input"))
    )
    (net (code "59") (name "/EMC_WE") (class "Default")
      (node (ref "U1") (pin "T4") (pinfunction "P1_6/GPIO1[9]/CTIN_5/~{EMC_WE}/~{EMC_BLS0}/SGPIO14/SD_CMD_T4") (pintype "bidirectional"))
      (node (ref "U2") (pin "F9") (pinfunction "WE#_F9") (pintype "input"))
    )
    (net (code "60") (name "/ENET_COL") (class "Default")
      (node (ref "H5") (pin "5") (pinfunction "5_5") (pintype "passive"))
      (node (ref "U1") (pin "L11") (pinfunction "P9_6/GPIO4[11]/MCOB1/USB1_PWR_FAULT/ENET_COL/SGPIO8/U0_RXD_L11") (pintype "bidirectional"))
    )
    (net (code "61") (name "/ENET_CRS") (class "Default")
      (node (ref "H5") (pin "20") (pinfunction "20_20") (pintype "passive"))
      (node (ref "U1") (pin "T1") (pinfunction "P9_0/GPIO4[12]/~{MCABORT}/ENET_CRS/SGPIO0/SSP0_SSEL_T1") (pintype "bidirectional"))
    )
    (net (code "62") (name "/ENET_MDIO") (class "Default")
      (node (ref "H5") (pin "13") (pinfunction "13_13") (pintype "passive"))
      (node (ref "U1") (pin "M8") (pinfunction "P1_17/GPIO0[12]/U2_UCLK/ENET_MDIO/T0_CAP3/CAN1_TD/SGPIO11_M8") (pintype "bidirectional"))
    )
    (net (code "63") (name "/ENET_RXD0") (class "Default")
      (node (ref "H5") (pin "3") (pinfunction "3_3") (pintype "passive"))
      (node (ref "U1") (pin "T12") (pinfunction "P1_15/GPIO0[2]/U2_TXD/SGPIO2/ENET_RXD0/T0_MAT1/EMC_D8_T12") (pintype "bidirectional"))
    )
    (net (code "64") (name "/ENET_RXD1") (class "Default")
      (node (ref "H5") (pin "30") (pinfunction "30_30") (pintype "passive"))
      (node (ref "U1") (pin "L3") (pinfunction "P0_0/GPIO0[0]/SSP1_MISO/ENET_RXD1/SGPIO0/I2S0_TX_WS/I2S1_TX_WS_L3") (pintype "bidirectional"))
    )
    (net (code "65") (name "/ENET_RXD2") (class "Default")
      (node (ref "H5") (pin "18") (pinfunction "18_18") (pintype "passive"))
      (node (ref "U1") (pin "M6") (pinfunction "P9_3/GPIO4[15]/MCOA0/USB1_IND1/ENET_RXD2/SGPIO9/U3_TXD_M6") (pintype "bidirectional"))
    )
    (net (code "66") (name "/ENET_RXD3") (class "Default")
      (node (ref "H5") (pin "11") (pinfunction "11_11") (pintype "passive"))
      (node (ref "U1") (pin "N8") (pinfunction "P9_2/GPIO4[14]/MCOB2/I2S0_TX_SDA/ENET_RXD3/SGPIO2/SSP0_MOSI_N8") (pintype "bidirectional"))
    )
    (net (code "67") (name "/ENET_RX_CLK") (class "Default")
      (node (ref "H5") (pin "27") (pinfunction "27_27") (pintype "passive"))
      (node (ref "U1") (pin "D4") (pinfunction "PC_0/USB1_ULPI_CLK/ENET_RX_CLK/LCD_DCLK/SD_CLK/ADC1_1_D4") (pintype "bidirectional"))
    )
    (net (code "68") (name "/ENET_RX_DV") (class "Default")
      (node (ref "H5") (pin "14") (pinfunction "14_14") (pintype "passive"))
      (node (ref "U1") (pin "M7") (pinfunction "P1_16/GPIO0[3]/U2_RXD/SGPIO3/ENET_CRS/T0_MAT0/EMC_D9/ENET_RX_DV_M7") (pintype "bidirectional"))
    )
    (net (code "69") (name "/ENET_RX_ER") (class "Default")
      (node (ref "H5") (pin "24") (pinfunction "24_24") (pintype "passive"))
      (node (ref "U1") (pin "N6") (pinfunction "P9_1/GPIO4[13]/MCOA2/I2S0_TX_WS/ENET_RX_ER/SGPIO1/SSP0_MISO_N6") (pintype "bidirectional"))
    )
    (net (code "70") (name "/ENET_TXD0") (class "Default")
      (node (ref "H5") (pin "4") (pinfunction "4_4") (pintype "passive"))
      (node (ref "U1") (pin "N12") (pinfunction "P1_18/GPIO0[13]/U2_DIR/ENET_TXD0/T0_MAT3/CAN1_RD/SGPIO12/EMC_D10_N12") (pintype "bidirectional"))
    )
    (net (code "71") (name "/ENET_TXD1") (class "Default")
      (node (ref "H5") (pin "8") (pinfunction "8_8") (pintype "passive"))
      (node (ref "U1") (pin "M10") (pinfunction "P1_20/GPIO0[15]/SSP1_SSEL/ENET_TXD1/T0_CAP2/SGPIO13/EMC_D11_M10") (pintype "bidirectional"))
    )
    (net (code "72") (name "/ENET_TXD2") (class "Default")
      (node (ref "H5") (pin "7") (pinfunction "7_7") (pintype "passive"))
      (node (ref "U1") (pin "N10") (pinfunction "P9_4/MCOB0/USB1_IND0/GPIO5[17]/ENET_TXD2/SGPIO4/U3_RXD_N10") (pintype "bidirectional"))
    )
    (net (code "73") (name "/ENET_TXD3") (class "Default")
      (node (ref "H5") (pin "9") (pinfunction "9_9") (pintype "passive"))
      (node (ref "U1") (pin "M9") (pinfunction "P9_5/MCOA1/USB1_PPWR/GPIO5[18]/ENET_TXD3/SGPIO3/U0_TXD_M9") (pintype "bidirectional"))
    )
    (net (code "74") (name "/ENET_TX_CLK") (class "Default")
      (node (ref "H5") (pin "6") (pinfunction "6_6") (pintype "passive"))
      (node (ref "U1") (pin "M11") (pinfunction "P1_19/ENET_TX_CLK(ENET_REF_CLK)/SSP1_SCK/CLKOUT/I2S0_RX_MCLK/I2S1_TX_SCK_M11") (pintype "bidirectional"))
    )
    (net (code "75") (name "/ENET_TX_EN") (class "Default")
      (node (ref "H5") (pin "28") (pinfunction "28_28") (pintype "passive"))
      (node (ref "U1") (pin "M2") (pinfunction "P0_1/GPIO0[1]/SSP1_MOSI/ENET_COL/SGPIO1/ENET_TX_EN/I2S1_TX_SDA_M2") (pintype "bidirectional"))
    )
    (net (code "76") (name "/I2C0_SCL") (class "Default")
      (node (ref "H3") (pin "12") (pinfunction "12_12") (pintype "passive"))
      (node (ref "U1") (pin "L15") (pinfunction "I2C0_SCL_L15") (pintype "bidirectional"))
    )
    (net (code "77") (name "/I2C0_SDA") (class "Default")
      (node (ref "H3") (pin "13") (pinfunction "13_13") (pintype "passive"))
      (node (ref "U1") (pin "L16") (pinfunction "I2C0_SDA_L16") (pintype "bidirectional"))
    )
    (net (code "78") (name "/LCD_DCLK") (class "Default")
      (node (ref "H1") (pin "31") (pinfunction "31_31") (pintype "passive"))
      (node (ref "U1") (pin "H4") (pinfunction "P4_7/LCD_DCLK/GP_CLKIN/I2S1_TX_SCK/I2S0_TX_SCK_H4") (pintype "bidirectional"))
    )
    (net (code "79") (name "/LCD_EN") (class "Default")
      (node (ref "H1") (pin "32") (pinfunction "32_32") (pintype "passive"))
      (node (ref "U1") (pin "C1") (pinfunction "P4_6/GPIO2[6]/CTOUT_4/LCD_ENAB/LCDM/SGPIO12_C1") (pintype "bidirectional"))
    )
    (net (code "80") (name "/LCD_FP") (class "Default")
      (node (ref "H1") (pin "30") (pinfunction "30_30") (pintype "passive"))
      (node (ref "U1") (pin "D2") (pinfunction "P4_5/GPIO2[5]/CTOUT_5/LCD_FP/SGPIO11_D2") (pintype "bidirectional"))
    )
    (net (code "81") (name "/LCD_VD0") (class "Default")
      (node (ref "H1") (pin "28") (pinfunction "28_28") (pintype "passive"))
      (node (ref "U1") (pin "A1") (pinfunction "P4_1/GPIO2[1]/CTOUT_1/LCD_VD0/LCD_VD19/U3_TXD/ENET_COL/ADC0_1_A1") (pintype "bidirectional"))
    )
    (net (code "82") (name "/LCD_VD1") (class "Default")
      (node (ref "H1") (pin "27") (pinfunction "27_27") (pintype "passive"))
      (node (ref "U1") (pin "B1") (pinfunction "P4_4/GPIO2[4]/CTOUT_2/LCD_VD1/LCD_VD20/U3_DIR/SGPIO10/DAC_B1") (pintype "bidirectional"))
    )
    (net (code "83") (name "/LCD_VD2") (class "Default")
      (node (ref "H1") (pin "26") (pinfunction "26_26") (pintype "passive"))
      (node (ref "U1") (pin "C2") (pinfunction "P4_3/GPIO2[3]/CTOUT_3/LCD_VD2/LCD_VD21/U3_BAUD/SGPIO9/ADC0_0_C2") (pintype "bidirectional"))
    )
    (net (code "84") (name "/LCD_VD3") (class "Default")
      (node (ref "H1") (pin "25") (pinfunction "25_25") (pintype "passive"))
      (node (ref "U1") (pin "D3") (pinfunction "P4_2/GPIO2[2]/CTOUT_0/LCD_VD3/LCD_VD12/U3_RXD/SGPIO8_D3") (pintype "bidirectional"))
    )
    (net (code "85") (name "/LCD_VD4") (class "Default")
      (node (ref "H1") (pin "24") (pinfunction "24_24") (pintype "passive"))
      (node (ref "U1") (pin "K1") (pinfunction "P8_7/GPIO4[7]/USB1_ULPI_STP/LCD_VD4/LCD_PWR/T0_CAP3_K1") (pintype "bidirectional"))
    )
    (net (code "86") (name "/LCD_VD5") (class "Default")
      (node (ref "H1") (pin "23") (pinfunction "23_23") (pintype "passive"))
      (node (ref "U1") (pin "K3") (pinfunction "P8_6/GPIO4[6]/USB1_ULPI_NXT/LCD_VD5/LCD_LP/T0_CAP2_K3") (pintype "bidirectional"))
    )
    (net (code "87") (name "/LCD_VD6") (class "Default")
      (node (ref "H1") (pin "22") (pinfunction "22_22") (pintype "passive"))
      (node (ref "U1") (pin "J1") (pinfunction "P8_5/GPIO4[5]/USB1_ULPI_D0/LCD_VD6/LCD_VD8/T0_CAP1_J1") (pintype "bidirectional"))
    )
    (net (code "88") (name "/LCD_VD7") (class "Default")
      (node (ref "H1") (pin "21") (pinfunction "21_21") (pintype "passive"))
      (node (ref "U1") (pin "J2") (pinfunction "P8_4/GPIO4[4]/USB1_ULPI_D1/LCD_VD7/LCD_VD16/T0_CAP0_J2") (pintype "bidirectional"))
    )
    (net (code "89") (name "/LCD_VD8") (class "Default")
      (node (ref "H1") (pin "20") (pinfunction "20_20") (pintype "passive"))
      (node (ref "U1") (pin "A7") (pinfunction "P7_5/GPIO3[13]/CTOUT_12/LCD_VD8/LCD_VD23/TRACEDATA[1]/ADC0_3_A7") (pintype "bidirectional"))
    )
    (net (code "90") (name "/LCD_VD9") (class "Default")
      (node (ref "H1") (pin "19") (pinfunction "19_19") (pintype "passive"))
      (node (ref "U1") (pin "E2") (pinfunction "P4_8/CTIN_5/LCD_VD9/GPIO5[12]/LCD_VD22/CAN1_TD/SGPIO13_E2") (pintype "bidirectional"))
    )
    (net (code "91") (name "/LCD_VD10") (class "Default")
      (node (ref "H1") (pin "18") (pinfunction "18_18") (pintype "passive"))
      (node (ref "U1") (pin "M3") (pinfunction "P4_10/CTIN_2/LCD_VD10/GPIO5[14]/LCD_VD14/SGPIO15_M3") (pintype "bidirectional"))
    )
    (net (code "92") (name "/LCD_VD11") (class "Default")
      (node (ref "H1") (pin "17") (pinfunction "17_17") (pintype "passive"))
      (node (ref "U1") (pin "L2") (pinfunction "P4_9/CTIN_6/LCD_VD11/GPIO5[13]/LCD_VD15/CAN1_RD/SGPIO14_L2") (pintype "bidirectional"))
    )
    (net (code "93") (name "/LCD_VD12") (class "Default")
      (node (ref "H1") (pin "16") (pinfunction "16_16") (pintype "passive"))
      (node (ref "U1") (pin "J3") (pinfunction "P8_3/GPIO4[3]/USB1_ULPI_D2/LCD_VD12/LCD_VD19/T0_MAT3_J3") (pintype "bidirectional"))
    )
    (net (code "94") (name "/LCD_VD13") (class "Default")
      (node (ref "H1") (pin "15") (pinfunction "15_15") (pintype "passive"))
      (node (ref "U1") (pin "A6") (pinfunction "PB_6/USB1_ULPI_D3/LCD_VD13/GPIO5[26]/CTIN_6/LCD_VD19/ADC0_6_A6") (pintype "bidirectional"))
    )
    (net (code "95") (name "/LCD_VD14") (class "Default")
      (node (ref "H1") (pin "14") (pinfunction "14_14") (pintype "passive"))
      (node (ref "U1") (pin "A12") (pinfunction "PB_5/USB1_ULPI_D4/LCD_VD14/GPIO5[25]/CTIN_7/LCD_PWR_A12") (pintype "bidirectional"))
    )
    (net (code "96") (name "/LCD_VD15") (class "Default")
      (node (ref "H1") (pin "13") (pinfunction "13_13") (pintype "passive"))
      (node (ref "U1") (pin "B11") (pinfunction "PB_4/USB1_ULPI_D5/LCD_VD15/GPIO5[24]/CTIN_5_B11") (pintype "bidirectional"))
    )
    (net (code "97") (name "/LCD_VD16") (class "Default")
      (node (ref "H1") (pin "12") (pinfunction "12_12") (pintype "passive"))
      (node (ref "U1") (pin "C8") (pinfunction "P7_4/GPIO3[12]/CTOUT_13/LCD_VD16/LCD_VD4/TRACEDATA[0]/ADC0_4_C8") (pintype "bidirectional"))
    )
    (net (code "98") (name "/LCD_VD17") (class "Default")
      (node (ref "H1") (pin "11") (pinfunction "11_11") (pintype "passive"))
      (node (ref "U1") (pin "C13") (pinfunction "P7_3/GPIO3[11]/CTIN_3/LCD_VD17/LCD_VD5_C13") (pintype "bidirectional"))
    )
    (net (code "99") (name "/LCD_VD18") (class "Default")
      (node (ref "H1") (pin "10") (pinfunction "10_10") (pintype "passive"))
      (node (ref "U1") (pin "A16") (pinfunction "P7_2/GPIO3[10]/CTIN_4/I2S0_TX_SDA/LCD_VD18/LCD_VD6/U2_RXD/SGPIO6_A16") (pintype "bidirectional"))
    )
    (net (code "100") (name "/LCD_VD19") (class "Default")
      (node (ref "H1") (pin "9") (pinfunction "9_9") (pintype "passive"))
      (node (ref "U1") (pin "C14") (pinfunction "P7_1/GPIO3[9]/CTOUT_15/I2S0_TX_WS/LCD_VD19/LCD_VD7/U2_TXD/SGPIO5_C14") (pintype "bidirectional"))
    )
    (net (code "101") (name "/LCD_VD20") (class "Default")
      (node (ref "H1") (pin "8") (pinfunction "8_8") (pintype "passive"))
      (node (ref "U1") (pin "A13") (pinfunction "PB_3/USB1_ULPI_D6/LCD_VD20/GPIO5[23]/CTOUT_8_A13") (pintype "bidirectional"))
    )
    (net (code "102") (name "/LCD_VD21") (class "Default")
      (node (ref "H1") (pin "7") (pinfunction "7_7") (pintype "passive"))
      (node (ref "U1") (pin "B12") (pinfunction "PB_2/USB1_ULPI_D7/LCD_VD21/GPIO5[22]/CTOUT_7_B12") (pintype "bidirectional"))
    )
    (net (code "103") (name "/LCD_VD22") (class "Default")
      (node (ref "H1") (pin "6") (pinfunction "6_6") (pintype "passive"))
      (node (ref "U1") (pin "A14") (pinfunction "PB_1/USB1_ULPI_DIR/LCD_VD22/GPIO5[21]/CTOUT_6_A14") (pintype "bidirectional"))
    )
    (net (code "104") (name "/LCD_VD23") (class "Default")
      (node (ref "H1") (pin "5") (pinfunction "5_5") (pintype "passive"))
      (node (ref "U1") (pin "B15") (pinfunction "PB_0/CTOUT_10/LCD_VD23/GPIO5[20]_B15") (pintype "bidirectional"))
    )
    (net (code "105") (name "/P1_3") (class "Default")
      (node (ref "H5") (pin "25") (pinfunction "25_25") (pintype "passive"))
      (node (ref "U1") (pin "P5") (pinfunction "P1_3/GPIO0[10]/CTOUT_8/SGPIO10/~{EMC_OE}/USB0_IND1/SSP1_MISO/SD_RST_P5") (pintype "bidirectional"))
    )
    (net (code "106") (name "/P1_4") (class "Default")
      (node (ref "H5") (pin "22") (pinfunction "22_22") (pintype "passive"))
      (node (ref "U1") (pin "T3") (pinfunction "P1_4/GPIO0[11]/CTOUT_9/SGPIO11/~{EMC_BLS0}/USB0_IND0/SSP1_MOSI/EMC_D15/SD_VOLT1_T3") (pintype "bidirectional"))
    )
    (net (code "107") (name "/P1_5") (class "Default")
      (node (ref "H5") (pin "17") (pinfunction "17_17") (pintype "passive"))
      (node (ref "U1") (pin "R5") (pinfunction "P1_5/GPIO1[8]/CTOUT_10/~{EMC_CS0}/USB0_PWR_FAULT/SSP1_SSEL/SGPIO15/SD_POW_R5") (pintype "bidirectional"))
    )
    (net (code "108") (name "/P2_3") (class "Default")
      (node (ref "H4") (pin "5") (pinfunction "5_5") (pintype "passive"))
      (node (ref "U1") (pin "J12") (pinfunction "P2_3/SGPIO12/I2C1_SDA/U3_TXD/CTIN_1/GPIO5[3]/T3_MAT0/USB0_PPWR_J12") (pintype "bidirectional"))
    )
    (net (code "109") (name "/P2_4") (class "Default")
      (node (ref "H4") (pin "7") (pinfunction "7_7") (pintype "passive"))
      (node (ref "U1") (pin "K11") (pinfunction "P2_4/SGPIO13/I2C1_SCL/U3_RXD/CTIN_0/GPIO5[4]/T3_MAT1/USB0_PWR_FAULT_K11") (pintype "bidirectional"))
    )
    (net (code "110") (name "/P2_5") (class "Default")
      (node (ref "H3") (pin "15") (pinfunction "15_15") (pintype "passive"))
      (node (ref "U1") (pin "K14") (pinfunction "P2_5/SGPIO14/CTIN_2/USB1_VBUS/ADCTRIG1/GPIO5[5]/T3_MAT2/USB0_IND0_K14") (pintype "bidirectional"))
    )
    (net (code "111") (name "/P3_0") (class "Default")
      (node (ref "H3") (pin "19") (pinfunction "19_19") (pintype "passive"))
      (node (ref "U1") (pin "F13") (pinfunction "P3_0/I2S0_RX_SCK/I2S0_RX_MCLK/I2S0_TX_SCK/I2S0_TX_MCLK/SSP0_SCK_F13") (pintype "bidirectional"))
    )
    (net (code "112") (name "/P3_1") (class "Default")
      (node (ref "H3") (pin "5") (pinfunction "5_5") (pintype "passive"))
      (node (ref "U1") (pin "G11") (pinfunction "P3_1/I2S0_TX_WS/I2S0_RX_WS/CAN0_RD/USB1_IND1/GPIO5[8]/LCD_VD15_G11") (pintype "bidirectional"))
    )
    (net (code "113") (name "/P3_2") (class "Default")
      (node (ref "H2") (pin "4") (pinfunction "4_4") (pintype "passive"))
      (node (ref "U1") (pin "F11") (pinfunction "P3_2/I2S0_TX_SDA/I2S0_RX_SDA/CAN0_TD/USB1_IND0/GPIO5[9]/LCD_VD14_F11") (pintype "bidirectional"))
    )
    (net (code "114") (name "/P3_3") (class "Default")
      (node (ref "H2") (pin "5") (pinfunction "5_5") (pintype "passive"))
      (node (ref "U1") (pin "B14") (pinfunction "P3_3/SPI_SCK/SSP0_SCK/SPIFI_SCK/CGU_OUT1/I2S0_TX_MCLK/I2S1_TX_SCK_B14") (pintype "bidirectional"))
    )
    (net (code "115") (name "/P3_4") (class "Default")
      (node (ref "H3") (pin "30") (pinfunction "30_30") (pintype "passive"))
      (node (ref "U1") (pin "A15") (pinfunction "P3_4/GPIO1[14]/SPIFI_SIO3/U1_TXD/I2S0_TX_WS/I2S1_RX_SDA/LCD_VD13_A15") (pintype "bidirectional"))
    )
    (net (code "116") (name "/P3_5") (class "Default")
      (node (ref "H2") (pin "12") (pinfunction "12_12") (pintype "passive"))
      (node (ref "U1") (pin "C12") (pinfunction "P3_5/GPIO1[15]/SPIFI_SIO2/U1_RXD/I2S0_TX_SDA/I2S1_RX_WS/LCD_VD12_C12") (pintype "bidirectional"))
    )
    (net (code "117") (name "/P3_6") (class "Default")
      (node (ref "H2") (pin "9") (pinfunction "9_9") (pintype "passive"))
      (node (ref "U1") (pin "B13") (pinfunction "P3_6/GPIO0[6]/SPI_MISO/SSP0_SSEL/SPIFI_MISO/SSP0_MISO_B13") (pintype "bidirectional"))
    )
    (net (code "118") (name "/P3_7") (class "Default")
      (node (ref "H2") (pin "13") (pinfunction "13_13") (pintype "passive"))
      (node (ref "U1") (pin "C11") (pinfunction "P3_7/SPI_MOSI/SSP0_MISO/SPIFI_MOSI/GPIO5[10]/SSP0_MOSI_C11") (pintype "bidirectional"))
    )
    (net (code "119") (name "/P3_8") (class "Default")
      (node (ref "H2") (pin "15") (pinfunction "15_15") (pintype "passive"))
      (node (ref "U1") (pin "C10") (pinfunction "P3_8/SPI_SSEL/SSP0_MOSI/SPIFI_CS/GPIO5[11]/SSP0_SSEL_C10") (pintype "bidirectional"))
    )
    (net (code "120") (name "/P4_0") (class "Default")
      (node (ref "H1") (pin "54") (pinfunction "54_54") (pintype "passive"))
      (node (ref "U1") (pin "D5") (pinfunction "P4_0/GPIO2[0]/MCOA0/NMI/LCD_VD13/U3_UCLK_D5") (pintype "bidirectional"))
    )
    (net (code "121") (name "/P6_0") (class "Default")
      (node (ref "H4") (pin "29") (pinfunction "29_29") (pintype "passive"))
      (node (ref "U1") (pin "M12") (pinfunction "P6_0/I2S0_RX_MCLK/I2S0_RX_SCK_M12") (pintype "bidirectional"))
    )
    (net (code "122") (name "/P6_1") (class "Default")
      (node (ref "H4") (pin "12") (pinfunction "12_12") (pintype "passive"))
      (node (ref "U1") (pin "R15") (pinfunction "P6_1/GPIO3[0]/~{EMC_DYCS1}/U0_UCLK/I2S0_RX_WS/T2_CAP0_R15") (pintype "bidirectional"))
    )
    (net (code "123") (name "/P6_2") (class "Default")
      (node (ref "H4") (pin "9") (pinfunction "9_9") (pintype "passive"))
      (node (ref "U1") (pin "L13") (pinfunction "P6_2/GPIO3[1]/EMC_CKEOUT1/U0_DIR/I2S0_RX_SDA/T2_CAP1_L13") (pintype "bidirectional"))
    )
    (net (code "124") (name "/P6_3") (class "Default")
      (node (ref "H4") (pin "11") (pinfunction "11_11") (pintype "passive"))
      (node (ref "U1") (pin "P15") (pinfunction "P6_3/GPIO3[2]/USB0_PPWR/SGPIO4/~{EMC_CS1}/T2_CAP2_P15") (pintype "bidirectional"))
    )
    (net (code "125") (name "/P6_6") (class "Default")
      (node (ref "H3") (pin "10") (pinfunction "10_10") (pintype "passive"))
      (node (ref "U1") (pin "L14") (pinfunction "P6_6/GPIO0[5]/~{EMC_BLS1}/SGPIO5/USB0_PWR_FAULT/T2_CAP3_L14") (pintype "bidirectional"))
    )
    (net (code "126") (name "/P6_7") (class "Default")
      (node (ref "H4") (pin "4") (pinfunction "4_4") (pintype "passive"))
      (node (ref "U1") (pin "J13") (pinfunction "P6_7/EMC_A15/SGPIO6/USB0_IND1/GPIO5[15]/T2_MAT0_J13") (pintype "bidirectional"))
    )
    (net (code "127") (name "/P7_0") (class "Default")
      (node (ref "H3") (pin "28") (pinfunction "28_28") (pintype "passive"))
      (node (ref "U1") (pin "B16") (pinfunction "P7_0/GPIO3[8]/CTOUT_14/LCD_LE/SGPIO4_B16") (pintype "bidirectional"))
    )
    (net (code "128") (name "/P7_6") (class "Default")
      (node (ref "H1") (pin "37") (pinfunction "37_37") (pintype "passive"))
      (node (ref "U1") (pin "C7") (pinfunction "P7_6/GPIO3[14]/CTOUT_11/LCD_LP/TRACEDATA[2]_C7") (pintype "bidirectional"))
    )
    (net (code "129") (name "/P7_7") (class "Default")
      (node (ref "H1") (pin "41") (pinfunction "41_41") (pintype "passive"))
      (node (ref "U1") (pin "B6") (pinfunction "P7_7/GPIO3[15]/CTOUT_8/LCD_PWR/TRACEDATA[3]/ENET_MDC/SGPIO7/ADC1_6_B6") (pintype "bidirectional"))
    )
    (net (code "130") (name "/P8_0") (class "Default")
      (node (ref "H1") (pin "39") (pinfunction "39_39") (pintype "passive"))
      (node (ref "U1") (pin "E5") (pinfunction "P8_0/GPIO4[0]/USB0_PWR_FAULT/MCI2/SGPIO8/T0_MAT0_E5") (pintype "bidirectional"))
    )
    (net (code "131") (name "/P8_1") (class "Default")
      (node (ref "H1") (pin "40") (pinfunction "40_40") (pintype "passive"))
      (node (ref "U1") (pin "H5") (pinfunction "P8_1/GPIO4[1]/USB0_IND1/MCI1/SGPIO9/T0_MAT1_H5") (pintype "bidirectional"))
    )
    (net (code "132") (name "/P8_2") (class "Default")
      (node (ref "H1") (pin "42") (pinfunction "42_42") (pintype "passive"))
      (node (ref "U1") (pin "K4") (pinfunction "P8_2/GPIO4[2]/USB0_IND0/MCI0/SGPIO10/T0_MAT2_K4") (pintype "bidirectional"))
    )
    (net (code "133") (name "/PA_0") (class "Default")
      (node (ref "H4") (pin "8") (pinfunction "8_8") (pintype "passive"))
      (node (ref "U1") (pin "L12") (pinfunction "PA_0/I2S1_RX_MCLK/CGU_OUT1_L12") (pintype "bidirectional"))
    )
    (net (code "134") (name "/PA_1") (class "Default")
      (node (ref "H3") (pin "17") (pinfunction "17_17") (pintype "passive"))
      (node (ref "U1") (pin "J14") (pinfunction "PA_1/GPIO4[8]/QEI_IDX/U2_TXD_J14") (pintype "bidirectional"))
    )
    (net (code "135") (name "/PA_2") (class "Default")
      (node (ref "H3") (pin "16") (pinfunction "16_16") (pintype "passive"))
      (node (ref "U1") (pin "K15") (pinfunction "PA_2/GPIO4[9]/QEI_PHB/U2_RXD_K15") (pintype "bidirectional"))
    )
    (net (code "136") (name "/PA_3") (class "Default")
      (node (ref "H4") (pin "3") (pinfunction "3_3") (pintype "passive"))
      (node (ref "U1") (pin "H11") (pinfunction "PA_3/GPIO4[10]/QEI_PHA_H11") (pintype "bidirectional"))
    )
    (net (code "137") (name "/PA_4") (class "Default")
      (node (ref "H3") (pin "6") (pinfunction "6_6") (pintype "passive"))
      (node (ref "U1") (pin "G13") (pinfunction "PA_4/CTOUT_9/EMC_A23/GPIO5[19]_G13") (pintype "bidirectional"))
    )
    (net (code "138") (name "/PC_13") (class "Default")
      (node (ref "H5") (pin "29") (pinfunction "29_29") (pintype "passive"))
      (node (ref "U1") (pin "M1") (pinfunction "PC_13/U1_TXD/GPIO6[12]/SGPIO12/I2S0_TX_WS/SD_DAT6_M1") (pintype "bidirectional"))
    )
    (net (code "139") (name "/PC_14") (class "Default")
      (node (ref "H1") (pin "60") (pinfunction "60_60") (pintype "passive"))
      (node (ref "U1") (pin "N1") (pinfunction "PC_14/U1_RXD/GPIO6[13]/SGPIO13/ENET_TX_ER/SD_DAT7_N1") (pintype "bidirectional"))
    )
    (net (code "140") (name "/PD_0") (class "Default")
      (node (ref "H1") (pin "53") (pinfunction "53_53") (pintype "passive"))
      (node (ref "U1") (pin "N2") (pinfunction "PD_0/CTOUT_15/EMC_DQMOUT2/GPIO6[14]/SGPIO4_N2") (pintype "bidirectional"))
    )
    (net (code "141") (name "/PD_1") (class "Default")
      (node (ref "H1") (pin "55") (pinfunction "55_55") (pintype "passive"))
      (node (ref "U1") (pin "P1") (pinfunction "PD_1/EMC_CKEOUT2/GPIO6[15]/SD_POW/SGPIO5_P1") (pintype "bidirectional"))
    )
    (net (code "142") (name "/PD_2") (class "Default")
      (node (ref "H5") (pin "26") (pinfunction "26_26") (pintype "passive"))
      (node (ref "U1") (pin "R1") (pinfunction "PD_2/CTOUT_7/EMC_D16/GPIO6[16]/SGPIO6_R1") (pintype "bidirectional"))
    )
    (net (code "143") (name "/PD_3") (class "Default")
      (node (ref "H5") (pin "23") (pinfunction "23_23") (pintype "passive"))
      (node (ref "U1") (pin "P4") (pinfunction "PD_3/CTOUT_6/EMC_D17/GPIO6[17]/SGPIO7_P4") (pintype "bidirectional"))
    )
    (net (code "144") (name "/PD_8") (class "Default")
      (node (ref "H5") (pin "12") (pinfunction "12_12") (pintype "passive"))
      (node (ref "U1") (pin "P8") (pinfunction "PD_8/CTIN_6/EMC_D22/GPIO6[22]/SGPIO12_P8") (pintype "bidirectional"))
    )
    (net (code "145") (name "/PD_9") (class "Default")
      (node (ref "H4") (pin "23") (pinfunction "23_23") (pintype "passive"))
      (node (ref "U1") (pin "T11") (pinfunction "PD_9/CTOUT_13/EMC_D23/GPIO6[23]/SGPIO13_T11") (pintype "bidirectional"))
    )
    (net (code "146") (name "/PD_10") (class "Default")
      (node (ref "H4") (pin "22") (pinfunction "22_22") (pintype "passive"))
      (node (ref "U1") (pin "P11") (pinfunction "PD_10/CTIN_1/~{EMC_BLS3}/GPIO6[24]_P11") (pintype "bidirectional"))
    )
    (net (code "147") (name "/PD_11") (class "Default")
      (node (ref "H5") (pin "10") (pinfunction "10_10") (pintype "passive"))
      (node (ref "U1") (pin "N9") (pinfunction "PD_11/~{EMC_CS3}/GPIO6[25]/USB1_ULPI_D0/CTOUT_14_N9") (pintype "bidirectional"))
    )
    (net (code "148") (name "/PD_12") (class "Default")
      (node (ref "H4") (pin "30") (pinfunction "30_30") (pintype "passive"))
      (node (ref "U1") (pin "N11") (pinfunction "PD_12/~{EMC_CS2}/GPIO6[26]/CTOUT_10_N11") (pintype "bidirectional"))
    )
    (net (code "149") (name "/PD_13") (class "Default")
      (node (ref "H4") (pin "16") (pinfunction "16_16") (pintype "passive"))
      (node (ref "U1") (pin "T14") (pinfunction "PD_13/CTIN_0/~{EMC_BLS2}/GPIO6[27]/CTOUT_13_T14") (pintype "bidirectional"))
    )
    (net (code "150") (name "/PD_14") (class "Default")
      (node (ref "H4") (pin "18") (pinfunction "18_18") (pintype "passive"))
      (node (ref "U1") (pin "R13") (pinfunction "PD_14/~{EMC_DYCS2}/GPIO6[28]/CTOUT_11_R13") (pintype "bidirectional"))
    )
    (net (code "151") (name "/PD_15") (class "Default")
      (node (ref "H4") (pin "14") (pinfunction "14_14") (pintype "passive"))
      (node (ref "U1") (pin "T15") (pinfunction "PD_15/EMC_A17/GPIO6[29]/SD_WP/CTOUT_8_T15") (pintype "bidirectional"))
    )
    (net (code "152") (name "/PD_16") (class "Default")
      (node (ref "H4") (pin "15") (pinfunction "15_15") (pintype "passive"))
      (node (ref "U1") (pin "R14") (pinfunction "PD_16/EMC_A16/GPIO6[30]/SD_VOLT2/CTOUT_12_R14") (pintype "bidirectional"))
    )
    (net (code "153") (name "/PE_0") (class "Default")
      (node (ref "H4") (pin "13") (pinfunction "13_13") (pintype "passive"))
      (node (ref "U1") (pin "P14") (pinfunction "PE_0/EMC_A18/GPIO7[0]/CAN1_TD_P14") (pintype "bidirectional"))
    )
    (net (code "154") (name "/PE_1") (class "Default")
      (node (ref "H4") (pin "10") (pinfunction "10_10") (pintype "passive"))
      (node (ref "U1") (pin "N14") (pinfunction "PE_1/EMC_A19/GPIO7[1]/CAN1_RD_N14") (pintype "bidirectional"))
    )
    (net (code "155") (name "/PE_2") (class "Default")
      (node (ref "H3") (pin "8") (pinfunction "8_8") (pintype "passive"))
      (node (ref "U1") (pin "M14") (pinfunction "PE_2/ADCTRIG0/CAN0_RD/EMC_A20/GPIO7[2]_M14") (pintype "bidirectional"))
    )
    (net (code "156") (name "/PE_3") (class "Default")
      (node (ref "H4") (pin "6") (pinfunction "6_6") (pintype "passive"))
      (node (ref "U1") (pin "K12") (pinfunction "PE_3/CAN0_TD/ADCTRIG1/EMC_A21/GPIO7[3]_K12") (pintype "bidirectional"))
    )
    (net (code "157") (name "/PE_4") (class "Default")
      (node (ref "H3") (pin "14") (pinfunction "14_14") (pintype "passive"))
      (node (ref "U1") (pin "K13") (pinfunction "PE_4/NMI/EMC_A22/GPIO7[4]_K13") (pintype "bidirectional"))
    )
    (net (code "158") (name "/PE_5") (class "Default")
      (node (ref "H3") (pin "7") (pinfunction "7_7") (pintype "passive"))
      (node (ref "U1") (pin "N16") (pinfunction "PE_5/CTOUT_3/U1_RTS/EMC_D24/GPIO7[5]_N16") (pintype "bidirectional"))
    )
    (net (code "159") (name "/PE_6") (class "Default")
      (node (ref "H3") (pin "11") (pinfunction "11_11") (pintype "passive"))
      (node (ref "U1") (pin "M16") (pinfunction "PE_6/CTOUT_2/U1_RI/EMC_D25/GPIO7[6]_M16") (pintype "bidirectional"))
    )
    (net (code "160") (name "/PE_7") (class "Default")
      (node (ref "H3") (pin "20") (pinfunction "20_20") (pintype "passive"))
      (node (ref "U1") (pin "F15") (pinfunction "PE_7/CTOUT_5/U1_CTS/EMC_D26/GPIO7[7]_F15") (pintype "bidirectional"))
    )
    (net (code "161") (name "/PE_8") (class "Default")
      (node (ref "H3") (pin "21") (pinfunction "21_21") (pintype "passive"))
      (node (ref "U1") (pin "F14") (pinfunction "PE_8/CTOUT_4/U1_DSR/EMC_D27/GPIO7[8]_F14") (pintype "bidirectional"))
    )
    (net (code "162") (name "/PE_9") (class "Default")
      (node (ref "H3") (pin "22") (pinfunction "22_22") (pintype "passive"))
      (node (ref "U1") (pin "E16") (pinfunction "PE_9/CTIN_4/U1_DCD/EMC_D28/GPIO7[9]_E16") (pintype "bidirectional"))
    )
    (net (code "163") (name "/PE_10") (class "Default")
      (node (ref "H3") (pin "24") (pinfunction "24_24") (pintype "passive"))
      (node (ref "U1") (pin "E14") (pinfunction "PE_10/CTIN_3/U1_DTR/EMC_D29/GPIO7[10]_E14") (pintype "bidirectional"))
    )
    (net (code "164") (name "/PE_11") (class "Default")
      (node (ref "H3") (pin "25") (pinfunction "25_25") (pintype "passive"))
      (node (ref "U1") (pin "D16") (pinfunction "PE_11/CTOUT_12/U1_TXD/EMC_D30/GPIO7[11]_D16") (pintype "bidirectional"))
    )
    (net (code "165") (name "/PE_12") (class "Default")
      (node (ref "H3") (pin "26") (pinfunction "26_26") (pintype "passive"))
      (node (ref "U1") (pin "D15") (pinfunction "PE_12/CTOUT_11/U1_RXD/EMC_D31/GPIO7[12]_D15") (pintype "bidirectional"))
    )
    (net (code "166") (name "/PE_13") (class "Default")
      (node (ref "H3") (pin "18") (pinfunction "18_18") (pintype "passive"))
      (node (ref "U1") (pin "G14") (pinfunction "PE_13/CTOUT_14/I2C1_SDA/EMC_DQMOUT3/GPIO7[13]_G14") (pintype "bidirectional"))
    )
    (net (code "167") (name "/PE_14") (class "Default")
      (node (ref "H3") (pin "29") (pinfunction "29_29") (pintype "passive"))
      (node (ref "U1") (pin "C15") (pinfunction "PE_14/~{EMC_DYCS3}/GPIO7[14]_C15") (pintype "bidirectional"))
    )
    (net (code "168") (name "/PE_15") (class "Default")
      (node (ref "H3") (pin "23") (pinfunction "23_23") (pintype "passive"))
      (node (ref "U1") (pin "E13") (pinfunction "PE_15/CTOUT_0/I2C1_SCL/EMC_CKEOUT3/GPIO7[15]_E13") (pintype "bidirectional"))
    )
    (net (code "169") (name "/PF_0") (class "Default")
      (node (ref "H2") (pin "8") (pinfunction "8_8") (pintype "passive"))
      (node (ref "U1") (pin "D12") (pinfunction "PF_0/SSP0_SCK/GP_CLKIN/I2S1_TX_MCLK_D12") (pintype "bidirectional"))
    )
    (net (code "170") (name "/PF_1") (class "Default")
      (node (ref "H2") (pin "7") (pinfunction "7_7") (pintype "passive"))
      (node (ref "U1") (pin "E11") (pinfunction "PF_1/SSP0_SSEL/GPIO7[16]/SGPIO0_E11") (pintype "bidirectional"))
    )
    (net (code "171") (name "/PF_2") (class "Default")
      (node (ref "H2") (pin "10") (pinfunction "10_10") (pintype "passive"))
      (node (ref "U1") (pin "D11") (pinfunction "PF_2/U3_TXD/SSP0_MISO/GPIO7[17]/SGPIO1_D11") (pintype "bidirectional"))
    )
    (net (code "172") (name "/PF_3") (class "Default")
      (node (ref "H2") (pin "3") (pinfunction "3_3") (pintype "passive"))
      (node (ref "U1") (pin "E10") (pinfunction "PF_3/U3_RXD/SSP0_MOSI/GPIO7[18]/SGPIO2_E10") (pintype "bidirectional"))
    )
    (net (code "173") (name "/PF_4") (class "Default")
      (node (ref "H2") (pin "16") (pinfunction "16_16") (pintype "passive"))
      (node (ref "U1") (pin "D10") (pinfunction "PF_4/SSP1_SCK/GP_CLKIN/TRACECLK/I2S0_TX_MCLK/I2S0_RX_SCK_D10") (pintype "bidirectional"))
    )
    (net (code "174") (name "/PF_5") (class "Default")
      (node (ref "H2") (pin "6") (pinfunction "6_6") (pintype "passive"))
      (node (ref "U1") (pin "E9") (pinfunction "PF_5/U3_UCLK/SSP1_SSEL/TRACEDATA[0]/GPIO7[19]/SGPIO4/ADC1_4_E9") (pintype "bidirectional"))
    )
    (net (code "175") (name "/PF_6") (class "Default")
      (node (ref "H1") (pin "36") (pinfunction "36_36") (pintype "passive"))
      (node (ref "U1") (pin "E7") (pinfunction "PF_6/U3_DIR/SSP1_MISO/TRACEDATA[1]/GPIO7[20]/SGPIO5/I2S1_TX_SDA/ADC1_3_E7") (pintype "bidirectional"))
    )
    (net (code "176") (name "/PF_7") (class "Default")
      (node (ref "H1") (pin "38") (pinfunction "38_38") (pintype "passive"))
      (node (ref "U1") (pin "B7") (pinfunction "PF_7/U3_BAUD/SSP1_MOSI/TRACEDATA[2]/GPIO7[21]/SGPIO6/I2S1_TX_WS/ADC1_7_B7") (pintype "bidirectional"))
    )
    (net (code "177") (name "/PF_8") (class "Default")
      (node (ref "H1") (pin "44") (pinfunction "44_44") (pintype "passive"))
      (node (ref "U1") (pin "E6") (pinfunction "PF_8/U0_UCLK/CTIN_2/TRACEDATA[3]/GPIO7[22]/SGPIO7/ADC0_2_E6") (pintype "bidirectional"))
    )
    (net (code "178") (name "/PF_9") (class "Default")
      (node (ref "H1") (pin "47") (pinfunction "47_47") (pintype "passive"))
      (node (ref "U1") (pin "D6") (pinfunction "PF_9/U0_DIR/CTOUT_1/GPIO7[23]/SGPIO3/ADC1_2_D6") (pintype "bidirectional"))
    )
    (net (code "179") (name "/PF_10") (class "Default")
      (node (ref "H1") (pin "51") (pinfunction "51_51") (pintype "passive"))
      (node (ref "U1") (pin "A3") (pinfunction "PF_10/U0_TXD/GPIO7[24]/SD_WP/ADC0_5_A3") (pintype "bidirectional"))
    )
    (net (code "180") (name "/PF_11") (class "Default")
      (node (ref "H1") (pin "57") (pinfunction "57_57") (pintype "passive"))
      (node (ref "U1") (pin "A2") (pinfunction "PF_11/U0_RXD/GPIO7[25]/SD_VOLT2/ADC1_5_A2") (pintype "bidirectional"))
    )
    (net (code "181") (name "/REFCLK") (class "Default")
      (node (ref "C34") (pin "1") (pinfunction "1_1") (pintype "passive"))
      (node (ref "R2") (pin "2") (pinfunction "2_2") (pintype "passive"))
      (node (ref "U3") (pin "21") (pinfunction "REFCLK/XI_21") (pintype "input"))
      (node (ref "X2") (pin "3") (pinfunction "3_3") (pintype "passive"))
    )
    (net (code "182") (name "/RESET") (class "Default")
      (node (ref "C36") (pin "1") (pinfunction "1_1") (pintype "passive"))
      (node (ref "H6") (pin "10") (pinfunction "RST_10") (pintype "passive"))
      (node (ref "R8") (pin "1") (pinfunction "1_1") (pintype "passive"))
      (node (ref "S1") (pin "2") (pinfunction "2_2") (pintype "passive"))
      (node (ref "U1") (pin "D9") (pinfunction "~{RESET}_D9") (pintype "input"))
    )
    (net (code "183") (name "/RTCX1") (class "Default")
      (node (ref "H2") (pin "19") (pinfunction "19_19") (pintype "passive"))
      (node (ref "U1") (pin "A8") (pinfunction "RTCX1_A8") (pintype "passive"))
    )
    (net (code "184") (name "/RTCX2") (class "Default")
      (node (ref "H2") (pin "20") (pinfunction "20_20") (pintype "passive"))
      (node (ref "U1") (pin "B8") (pinfunction "RTCX2_B8") (pintype "passive"))
    )
    (net (code "185") (name "/RTC_ALARM") (class "Default")
      (node (ref "H2") (pin "11") (pinfunction "11_11") (pintype "passive"))
      (node (ref "U1") (pin "A11") (pinfunction "RTC_ALARM_A11") (pintype "output"))
    )
    (net (code "186") (name "/SAMPLE") (class "Default")
      (node (ref "H2") (pin "18") (pinfunction "18_18") (pintype "passive"))
      (node (ref "U1") (pin "B9") (pinfunction "~{SAMPLE}_B9") (pintype "passive"))
    )
    (net (code "187") (name "/TCK") (class "Default")
      (node (ref "H6") (pin "4") (pinfunction "TCK_4") (pintype "passive"))
      (node (ref "R7") (pin "2") (pinfunction "2_2") (pintype "passive"))
      (node (ref "U1") (pin "J5") (pinfunction "TCK/SWDCLK_J5") (pintype "input"))
    )
    (net (code "188") (name "/TDI") (class "Default")
      (node (ref "H6") (pin "8") (pinfunction "TDI_8") (pintype "passive"))
      (node (ref "R3") (pin "1") (pinfunction "1_1") (pintype "passive"))
      (node (ref "U1") (pin "J4") (pinfunction "TDI_J4") (pintype "input"))
    )
    (net (code "189") (name "/TDO") (class "Default")
      (node (ref "H6") (pin "6") (pinfunction "TDO_6") (pintype "passive"))
      (node (ref "R4") (pin "1") (pinfunction "1_1") (pintype "passive"))
      (node (ref "U1") (pin "K5") (pinfunction "TDO/SWO_K5") (pintype "output"))
    )
    (net (code "190") (name "/TMS") (class "Default")
      (node (ref "H6") (pin "2") (pinfunction "TMS_2") (pintype "passive"))
      (node (ref "R5") (pin "1") (pinfunction "1_1") (pintype "passive"))
      (node (ref "U1") (pin "K6") (pinfunction "TMS/SWDIO_K6") (pintype "bidirectional"))
    )
    (net (code "191") (name "/TRST") (class "Default")
      (node (ref "R6") (pin "1") (pinfunction "1_1") (pintype "passive"))
      (node (ref "TP1") (pin "1") (pintype "passive"))
      (node (ref "U1") (pin "M4") (pinfunction "~{TRST}_M4") (pintype "input"))
    )
    (net (code "192") (name "/ULPI_CLKOUT") (class "Default")
      (node (ref "U1") (pin "L1") (pinfunction "P8_8/USB1_ULPI_CLK/CGU_OUT0/I2S1_TX_MCLK_L1") (pintype "bidirectional"))
      (node (ref "U3") (pin "2") (pinfunction "CLKOUT_2") (pintype "tri_state"))
    )
    (net (code "193") (name "/ULPI_D0") (class "Default")
      (node (ref "U1") (pin "N4") (pinfunction "PC_8/USB1_ULPI_D0/ENET_RX_DV/GPIO6[7]/T3_MAT1/SD_CD_N4") (pintype "bidirectional"))
      (node (ref "U3") (pin "4") (pinfunction "DATA[0]_4") (pintype "bidirectional"))
    )
    (net (code "194") (name "/ULPI_D1") (class "Default")
      (node (ref "U1") (pin "G5") (pinfunction "PC_7/USB1_ULPI_D1/ENET_RXD3/GPIO6[6]/T3_MAT0/SD_DAT3_G5") (pintype "bidirectional"))
      (node (ref "U3") (pin "5") (pinfunction "DATA[1]_5") (pintype "bidirectional"))
    )
    (net (code "195") (name "/ULPI_D2") (class "Default")
      (node (ref "U1") (pin "H6") (pinfunction "PC_6/USB1_ULPI_D2/ENET_RXD2/GPIO6[5]/T3_CAP3/SD_DAT2_H6") (pintype "bidirectional"))
      (node (ref "U3") (pin "6") (pinfunction "DATA[2]_6") (pintype "bidirectional"))
    )
    (net (code "196") (name "/ULPI_D3") (class "Default")
      (node (ref "U1") (pin "G4") (pinfunction "PC_5/USB1_ULPI_D3/ENET_TX_ER/GPIO6[4]/T3_CAP2/SD_DAT1_G4") (pintype "bidirectional"))
      (node (ref "U3") (pin "7") (pinfunction "DATA[3]_7") (pintype "bidirectional"))
    )
    (net (code "197") (name "/ULPI_D4") (class "Default")
      (node (ref "U1") (pin "F4") (pinfunction "PC_4/USB1_ULPI_D4/ENET_TX_EN/GPIO6[3]/T3_CAP1/SD_DAT0_F4") (pintype "bidirectional"))
      (node (ref "U3") (pin "8") (pinfunction "DATA[4]_8") (pintype "bidirectional"))
    )
    (net (code "198") (name "/ULPI_D5") (class "Default")
      (node (ref "U1") (pin "F5") (pinfunction "PC_3/USB1_ULPI_D5/U1_RTS/ENET_TXD3/GPIO6[2]/SD_VOLT1/ADC1_0_F5") (pintype "bidirectional"))
      (node (ref "U3") (pin "10") (pinfunction "DATA[5]_10") (pintype "bidirectional"))
    )
    (net (code "199") (name "/ULPI_D6") (class "Default")
      (node (ref "U1") (pin "F6") (pinfunction "PC_2/USB1_ULPI_D6/U1_CTS/ENET_TXD2/GPIO6[1]/SD_RST_F6") (pintype "bidirectional"))
      (node (ref "U3") (pin "11") (pinfunction "DATA[6]_11") (pintype "bidirectional"))
    )
    (net (code "200") (name "/ULPI_D7") (class "Default")
      (node (ref "U1") (pin "E4") (pinfunction "PC_1/USB1_ULPI_D7/U1_RI/ENET_MDC/GPIO6[0]/T3_CAP0/SD_VOLT0_E4") (pintype "bidirectional"))
      (node (ref "U3") (pin "12") (pinfunction "DATA[7]_12") (pintype "bidirectional"))
    )
    (net (code "201") (name "/ULPI_DIR") (class "Default")
      (node (ref "U1") (pin "L5") (pinfunction "PC_11/USB1_ULPI_DIR/U1_DCD/GPIO6[10]/SD_DAT4_L5") (pintype "bidirectional"))
      (node (ref "U3") (pin "1") (pinfunction "DIR_1") (pintype "tri_state"))
    )
    (net (code "202") (name "/ULPI_NXT") (class "Default")
      (node (ref "U1") (pin "K2") (pinfunction "PC_9/USB1_ULPI_NXT/ENET_RX_ER/GPIO6[8]/T3_MAT2/SD_POW_K2") (pintype "bidirectional"))
      (node (ref "U3") (pin "3") (pinfunction "NXT_3") (pintype "output"))
    )
    (net (code "203") (name "/ULPI_RESET") (class "Default")
      (node (ref "U1") (pin "L6") (pinfunction "PC_12/U1_DTR/GPIO6[11]/SGPIO11/I2S0_TX_SDA/SD_DAT5_L6") (pintype "bidirectional"))
      (node (ref "U3") (pin "22") (pinfunction "RESETB_22") (pintype "input"))
    )
    (net (code "204") (name "/ULPI_STP") (class "Default")
      (node (ref "U1") (pin "M5") (pinfunction "PC_10/USB1_ULPI_STP/U1_DSR/GPIO6[9]/T3_MAT3/SD_CMD_M5") (pintype "bidirectional"))
      (node (ref "U3") (pin "24") (pinfunction "STP_24") (pintype "input"))
    )
    (net (code "205") (name "/USB0_D_N") (class "Default")
      (node (ref "J2") (pin "2") (pinfunction "SIG-_2") (pintype "passive"))
      (node (ref "U1") (pin "G2") (pinfunction "USB0_DM_G2") (pintype "bidirectional"))
    )
    (net (code "206") (name "/USB0_D_P") (class "Default")
      (node (ref "J2") (pin "3") (pinfunction "SIG+_3") (pintype "passive"))
      (node (ref "U1") (pin "F2") (pinfunction "USB0_DP_F2") (pintype "bidirectional"))
    )
    (net (code "207") (name "/USB0_ID") (class "Default")
      (node (ref "J2") (pin "4") (pintype "passive"))
      (node (ref "U1") (pin "H2") (pinfunction "USB0_ID_H2") (pintype "input"))
    )
    (net (code "208") (name "/USB1_DM") (class "Default")
      (node (ref "U1") (pin "G12") (pinfunction "USB1_DM_G12") (pintype "bidirectional+no_connect"))
    )
    (net (code "209") (name "/USB1_DP") (class "Default")
      (node (ref "U1") (pin "F12") (pinfunction "USB1_DP_F12") (pintype "bidirectional+no_connect"))
    )
    (net (code "210") (name "/VBUS") (class "Default")
      (node (ref "R12") (pin "2") (pinfunction "2_2") (pintype "passive"))
      (node (ref "U3") (pin "17") (pinfunction "VBUS_17") (pintype "power_in"))
    )
    (net (code "211") (name "/WAKEUP0") (class "Default")
      (node (ref "H2") (pin "17") (pinfunction "17_17") (pintype "passive"))
      (node (ref "U1") (pin "A9") (pinfunction "WAKEUP0_A9") (pintype "input"))
    )
    (net (code "212") (name "/WAKEUP1") (class "Default")
      (node (ref "H2") (pin "14") (pinfunction "14_14") (pintype "passive"))
      (node (ref "U1") (pin "A10") (pinfunction "WAKEUP1_A10") (pintype "input"))
    )
    (net (code "213") (name "/WAKEUP2") (class "Default")
      (node (ref "H1") (pin "34") (pinfunction "34_34") (pintype "passive"))
      (node (ref "U1") (pin "C9") (pinfunction "WAKEUP2_C9") (pintype "input"))
    )
    (net (code "214") (name "/WAKEUP3") (class "Default")
      (node (ref "H1") (pin "35") (pinfunction "35_35") (pintype "passive"))
      (node (ref "U1") (pin "D8") (pinfunction "WAKEUP3_D8") (pintype "input"))
    )
    (net (code "215") (name "/XO") (class "Default")
      (node (ref "C35") (pin "1") (pinfunction "1_1") (pintype "passive"))
      (node (ref "R2") (pin "1") (pinfunction "1_1") (pintype "passive"))
      (node (ref "U3") (pin "20") (pinfunction "XO_20") (pintype "passive"))
      (node (ref "X2") (pin "1") (pinfunction "1_1") (pintype "passive"))
    )
    (net (code "216") (name "/XTAL1") (class "Default")
      (node (ref "C38") (pin "1") (pinfunction "1_1") (pintype "passive"))
      (node (ref "R9") (pin "1") (pinfunction "1_1") (pintype "passive"))
      (node (ref "U1") (pin "D1") (pinfunction "XTAL1_D1") (pintype "passive"))
      (node (ref "X1") (pin "1") (pinfunction "1_1") (pintype "passive"))
    )
    (net (code "217") (name "/XTAL2") (class "Default")
      (node (ref "C37") (pin "1") (pinfunction "1_1") (pintype "passive"))
      (node (ref "R9") (pin "2") (pinfunction "2_2") (pintype "passive"))
      (node (ref "U1") (pin "E1") (pinfunction "XTAL2_E1") (pintype "passive"))
      (node (ref "X1") (pin "3") (pinfunction "3_3") (pintype "passive"))
    )
    (net (code "218") (name "3V3") (class "Default")
      (node (ref "C1") (pin "1") (pinfunction "1_1") (pintype "passive"))
      (node (ref "C10") (pin "1") (pinfunction "1_1") (pintype "passive"))
      (node (ref "C11") (pin "1") (pinfunction "1_1") (pintype "passive"))
      (node (ref "C12") (pin "1") (pinfunction "1_1") (pintype "passive"))
      (node (ref "C13") (pin "1") (pinfunction "1_1") (pintype "passive"))
      (node (ref "C14") (pin "1") (pinfunction "1_1") (pintype "passive"))
      (node (ref "C15") (pin "1") (pinfunction "1_1") (pintype "passive"))
      (node (ref "C16") (pin "1") (pinfunction "1_1") (pintype "passive"))
      (node (ref "C17") (pin "1") (pinfunction "1_1") (pintype "passive"))
      (node (ref "C18") (pin "1") (pinfunction "1_1") (pintype "passive"))
      (node (ref "C19") (pin "1") (pinfunction "1_1") (pintype "passive"))
      (node (ref "C2") (pin "1") (pinfunction "1_1") (pintype "passive"))
      (node (ref "C20") (pin "1") (pinfunction "1_1") (pintype "passive"))
      (node (ref "C21") (pin "1") (pinfunction "1_1") (pintype "passive"))
      (node (ref "C3") (pin "1") (pinfunction "1_1") (pintype "passive"))
      (node (ref "C4") (pin "1") (pinfunction "1_1") (pintype "passive"))
      (node (ref "C40") (pin "1") (pinfunction "1_1") (pintype "passive"))
      (node (ref "C5") (pin "1") (pinfunction "1_1") (pintype "passive"))
      (node (ref "C6") (pin "1") (pinfunction "1_1") (pintype "passive"))
      (node (ref "C7") (pin "1") (pinfunction "1_1") (pintype "passive"))
      (node (ref "C8") (pin "1") (pinfunction "1_1") (pintype "passive"))
      (node (ref "C9") (pin "1") (pinfunction "1_1") (pintype "passive"))
      (node (ref "D2") (pin "1") (pinfunction "ANODE_1") (pintype "passive"))
      (node (ref "FB2") (pin "1") (pinfunction "1_1") (pintype "passive"))
      (node (ref "FB4") (pin "2") (pinfunction "2_2") (pintype "passive"))
      (node (ref "FB5") (pin "2") (pinfunction "2_2") (pintype "passive"))
      (node (ref "FB6") (pin "1") (pinfunction "1_1") (pintype "passive"))
      (node (ref "FB7") (pin "1") (pinfunction "1_1") (pintype "passive"))
      (node (ref "H1") (pin "2") (pinfunction "2_2") (pintype "passive"))
      (node (ref "H2") (pin "2") (pinfunction "2_2") (pintype "passive"))
      (node (ref "H3") (pin "2") (pinfunction "2_2") (pintype "passive"))
      (node (ref "H4") (pin "2") (pinfunction "2_2") (pintype "passive"))
      (node (ref "H5") (pin "2") (pinfunction "2_2") (pintype "passive"))
      (node (ref "H6") (pin "1") (pinfunction "Vcc_1") (pintype "passive"))
      (node (ref "R13") (pin "2") (pinfunction "2_2") (pintype "passive"))
      (node (ref "R14") (pin "2") (pinfunction "2_2") (pintype "passive"))
      (node (ref "R3") (pin "2") (pinfunction "2_2") (pintype "passive"))
      (node (ref "R4") (pin "2") (pinfunction "2_2") (pintype "passive"))
      (node (ref "R5") (pin "2") (pinfunction "2_2") (pintype "passive"))
      (node (ref "R6") (pin "2") (pinfunction "2_2") (pintype "passive"))
      (node (ref "R8") (pin "2") (pinfunction "2_2") (pintype "passive"))
      (node (ref "U1") (pin "B10") (pinfunction "VBAT_B10") (pintype "power_in"))
      (node (ref "U1") (pin "D7") (pinfunction "VDDIO_D7") (pintype "power_in"))
      (node (ref "U1") (pin "E12") (pinfunction "VDDIO_E12") (pintype "power_in"))
      (node (ref "U1") (pin "E8") (pinfunction "VPP_E8") (pintype "power_in"))
      (node (ref "U1") (pin "F10") (pinfunction "VDDREG_F10") (pintype "power_in"))
      (node (ref "U1") (pin "F3") (pinfunction "USB0_VDDA3V3_DRIVER_F3") (pintype "power_in"))
      (node (ref "U1") (pin "F7") (pinfunction "VDDIO_F7") (pintype "power_in"))
      (node (ref "U1") (pin "F8") (pinfunction "VDDIO_F8") (pintype "power_in"))
      (node (ref "U1") (pin "F9") (pinfunction "VDDREG_F9") (pintype "power_in"))
      (node (ref "U1") (pin "G10") (pinfunction "VDDIO_G10") (pintype "power_in"))
      (node (ref "U1") (pin "G3") (pinfunction "USB0_VDDA3V3_G3") (pintype "power_in"))
      (node (ref "U1") (pin "H10") (pinfunction "VDDIO_H10") (pintype "power_in"))
      (node (ref "U1") (pin "J6") (pinfunction "VDDIO_J6") (pintype "power_in"))
      (node (ref "U1") (pin "J7") (pinfunction "VDDIO_J7") (pintype "power_in"))
      (node (ref "U1") (pin "K7") (pinfunction "VDDIO_K7") (pintype "power_in"))
      (node (ref "U1") (pin "L10") (pinfunction "VDDIO_L10") (pintype "power_in"))
      (node (ref "U1") (pin "L7") (pinfunction "VDDREG_L7") (pintype "power_in"))
      (node (ref "U1") (pin "L8") (pinfunction "VDDREG_L8") (pintype "power_in"))
      (node (ref "U1") (pin "L9") (pinfunction "VDDIO_L9") (pintype "power_in"))
      (node (ref "U1") (pin "N13") (pinfunction "VDDIO_N13") (pintype "power_in"))
      (node (ref "U1") (pin "N7") (pinfunction "VDDIO_N7") (pintype "power_in"))
      (node (ref "U4") (pin "2") (pinfunction "Vout_2") (pintype "power_in"))
      (node (ref "U5") (pin "2") (pinfunction "VIN_2") (pintype "power_in"))
    )
    (net (code "219") (name "GND") (class "Default")
      (node (ref "C1") (pin "2") (pinfunction "2_2") (pintype "passive"))
      (node (ref "C10") (pin "2") (pinfunction "2_2") (pintype "passive"))
      (node (ref "C11") (pin "2") (pinfunction "2_2") (pintype "passive"))
      (node (ref "C12") (pin "2") (pinfunction "2_2") (pintype "passive"))
      (node (ref "C13") (pin "2") (pinfunction "2_2") (pintype "passive"))
      (node (ref "C14") (pin "2") (pinfunction "2_2") (pintype "passive"))
      (node (ref "C15") (pin "2") (pinfunction "2_2") (pintype "passive"))
      (node (ref "C16") (pin "2") (pinfunction "2_2") (pintype "passive"))
      (node (ref "C17") (pin "2") (pinfunction "2_2") (pintype "passive"))
      (node (ref "C18") (pin "2") (pinfunction "2_2") (pintype "passive"))
      (node (ref "C19") (pin "2") (pinfunction "2_2") (pintype "passive"))
      (node (ref "C2") (pin "2") (pinfunction "2_2") (pintype "passive"))
      (node (ref "C20") (pin "2") (pinfunction "2_2") (pintype "passive"))
      (node (ref "C21") (pin "2") (pinfunction "2_2") (pintype "passive"))
      (node (ref "C22") (pin "2") (pinfunction "2_2") (pintype "passive"))
      (node (ref "C23") (pin "2") (pinfunction "2_2") (pintype "passive"))
      (node (ref "C24") (pin "2") (pinfunction "2_2") (pintype "passive"))
      (node (ref "C25") (pin "2") (pinfunction "2_2") (pintype "passive"))
      (node (ref "C26") (pin "2") (pinfunction "2_2") (pintype "passive"))
      (node (ref "C27") (pin "2") (pinfunction "2_2") (pintype "passive"))
      (node (ref "C28") (pin "2") (pinfunction "2_2") (pintype "passive"))
      (node (ref "C29") (pin "2") (pinfunction "2_2") (pintype "passive"))
      (node (ref "C3") (pin "2") (pinfunction "2_2") (pintype "passive"))
      (node (ref "C30") (pin "2") (pinfunction "2_2") (pintype "passive"))
      (node (ref "C31") (pin "2") (pinfunction "2_2") (pintype "passive"))
      (node (ref "C32") (pin "2") (pinfunction "2_2") (pintype "passive"))
      (node (ref "C33") (pin "2") (pinfunction "2_2") (pintype "passive"))
      (node (ref "C34") (pin "2") (pinfunction "2_2") (pintype "passive"))
      (node (ref "C35") (pin "2") (pinfunction "2_2") (pintype "passive"))
      (node (ref "C36") (pin "2") (pinfunction "2_2") (pintype "passive"))
      (node (ref "C37") (pin "2") (pinfunction "2_2") (pintype "passive"))
      (node (ref "C38") (pin "2") (pinfunction "2_2") (pintype "passive"))
      (node (ref "C39") (pin "2") (pinfunction "2_2") (pintype "passive"))
      (node (ref "C4") (pin "2") (pinfunction "2_2") (pintype "passive"))
      (node (ref "C40") (pin "2") (pinfunction "2_2") (pintype "passive"))
      (node (ref "C5") (pin "2") (pinfunction "2_2") (pintype "passive"))
      (node (ref "C6") (pin "2") (pinfunction "2_2") (pintype "passive"))
      (node (ref "C7") (pin "2") (pinfunction "2_2") (pintype "passive"))
      (node (ref "C8") (pin "2") (pinfunction "2_2") (pintype "passive"))
      (node (ref "C9") (pin "2") (pinfunction "2_2") (pintype "passive"))
      (node (ref "FB3") (pin "1") (pinfunction "1_1") (pintype "passive"))
      (node (ref "H1") (pin "1") (pinfunction "1_1") (pintype "passive"))
      (node (ref "H1") (pin "29") (pinfunction "29_29") (pintype "passive"))
      (node (ref "H1") (pin "3") (pinfunction "3_3") (pintype "passive"))
      (node (ref "H1") (pin "33") (pinfunction "33_33") (pintype "passive"))
      (node (ref "H1") (pin "4") (pinfunction "4_4") (pintype "passive"))
      (node (ref "H1") (pin "59") (pinfunction "59_59") (pintype "passive"))
      (node (ref "H2") (pin "1") (pinfunction "1_1") (pintype "passive"))
      (node (ref "H3") (pin "1") (pinfunction "1_1") (pintype "passive"))
      (node (ref "H3") (pin "9") (pinfunction "9_9") (pintype "passive"))
      (node (ref "H4") (pin "1") (pinfunction "1_1") (pintype "passive"))
      (node (ref "H4") (pin "17") (pinfunction "17_17") (pintype "passive"))
      (node (ref "H4") (pin "20") (pinfunction "20_20") (pintype "passive"))
      (node (ref "H4") (pin "21") (pinfunction "21_21") (pintype "passive"))
      (node (ref "H4") (pin "24") (pinfunction "24_24") (pintype "passive"))
      (node (ref "H4") (pin "25") (pinfunction "25_25") (pintype "passive"))
      (node (ref "H4") (pin "27") (pinfunction "27_27") (pintype "passive"))
      (node (ref "H4") (pin "28") (pinfunction "28_28") (pintype "passive"))
      (node (ref "H5") (pin "1") (pinfunction "1_1") (pintype "passive"))
      (node (ref "H6") (pin "3") (pinfunction "GND_3") (pintype "passive"))
      (node (ref "H6") (pin "5") (pinfunction "GND_5") (pintype "passive"))
      (node (ref "H6") (pin "9") (pinfunction "GND_9") (pintype "passive"))
      (node (ref "J1") (pin "4") (pinfunction "GND_4") (pintype "power_in"))
      (node (ref "J1") (pin "MH") (pinfunction "SHLD_MH") (pintype "passive"))
      (node (ref "J2") (pin "5") (pinfunction "GND_5") (pintype "passive"))
      (node (ref "J2") (pin "MH") (pinfunction "MH_MH") (pintype "passive"))
      (node (ref "J3") (pin "4") (pinfunction "GND_4") (pintype "passive"))
      (node (ref "J3") (pin "SH") (pinfunction "SHLD_SH") (pintype "passive"))
      (node (ref "R1") (pin "1") (pinfunction "1_1") (pintype "passive"))
      (node (ref "R10") (pin "1") (pinfunction "1_1") (pintype "passive"))
      (node (ref "R11") (pin "1") (pinfunction "1_1") (pintype "passive"))
      (node (ref "R7") (pin "1") (pinfunction "1_1") (pintype "passive"))
      (node (ref "S1") (pin "3") (pinfunction "3_3") (pintype "passive"))
      (node (ref "S1") (pin "4") (pinfunction "4_4") (pintype "passive"))
      (node (ref "S1") (pin "5") (pinfunction "GND_5") (pintype "passive"))
      (node (ref "U1") (pin "C4") (pinfunction "VSSIO_C4") (pintype "power_in"))
      (node (ref "U1") (pin "D13") (pinfunction "VSSIO_D13") (pintype "power_in"))
      (node (ref "U1") (pin "G1") (pinfunction "USB0_VSSA_REF_G1") (pintype "power_in"))
      (node (ref "U1") (pin "G6") (pinfunction "VSSIO_G6") (pintype "power_in"))
      (node (ref "U1") (pin "G7") (pinfunction "VSSIO_G7") (pintype "power_in"))
      (node (ref "U1") (pin "G8") (pinfunction "VSSIO_G8") (pintype "power_in"))
      (node (ref "U1") (pin "G9") (pinfunction "VSS_G9") (pintype "power_in"))
      (node (ref "U1") (pin "H3") (pinfunction "USB0_VSSA_TERM_H3") (pintype "power_in"))
      (node (ref "U1") (pin "H7") (pinfunction "VSS_H7") (pintype "power_in"))
      (node (ref "U1") (pin "H8") (pinfunction "VSSIO_H8") (pintype "power_in"))
      (node (ref "U1") (pin "H9") (pinfunction "VSSIO_H9") (pintype "power_in"))
      (node (ref "U1") (pin "J10") (pinfunction "VSS_J10") (pintype "power_in"))
      (node (ref "U1") (pin "J11") (pinfunction "VSS_J11") (pintype "power_in"))
      (node (ref "U1") (pin "J8") (pinfunction "VSSIO_J8") (pintype "power_in"))
      (node (ref "U1") (pin "J9") (pinfunction "VSSIO_J9") (pintype "power_in"))
      (node (ref "U1") (pin "K10") (pinfunction "VSSIO_K10") (pintype "power_in"))
      (node (ref "U1") (pin "K8") (pinfunction "VSS_K8") (pintype "power_in"))
      (node (ref "U1") (pin "K9") (pinfunction "VSSIO_K9") (pintype "power_in"))
      (node (ref "U1") (pin "M13") (pinfunction "VSSIO_M13") (pintype "power_in"))
      (node (ref "U1") (pin "P13") (pinfunction "VSSIO_P13") (pintype "power_in"))
      (node (ref "U1") (pin "P7") (pinfunction "VSSIO_P7") (pintype "power_in"))
      (node (ref "U2") (pin "A1") (pinfunction "VSS_A1") (pintype "power_in"))
      (node (ref "U2") (pin "A3") (pinfunction "VSSQ_A3") (pintype "power_in"))
      (node (ref "U2") (pin "B7") (pinfunction "VSSQ_B7") (pintype "power_in"))
      (node (ref "U2") (pin "C3") (pinfunction "VSSQ_C3") (pintype "power_in"))
      (node (ref "U2") (pin "D7") (pinfunction "VSSQ_D7") (pintype "power_in"))
      (node (ref "U2") (pin "E3") (pinfunction "VSS_E3") (pintype "power_in"))
      (node (ref "U2") (pin "J1") (pinfunction "VSS_J1") (pintype "power_in"))
      (node (ref "U3") (pin "18") (pinfunction "ID_18") (pintype "input"))
      (node (ref "U3") (pin "25") (pinfunction "GND_25") (pintype "power_in"))
      (node (ref "U4") (pin "3") (pinfunction "GND_3") (pintype "power_in"))
      (node (ref "U5") (pin "1") (pinfunction "GND_1") (pintype "power_in"))
      (node (ref "X1") (pin "2") (pinfunction "GND_2") (pintype "passive"))
      (node (ref "X1") (pin "4") (pinfunction "GND_4") (pintype "passive"))
      (node (ref "X2") (pin "2") (pinfunction "GND_2") (pintype "passive"))
      (node (ref "X2") (pin "4") (pinfunction "GND_4") (pintype "passive"))
    )
    (net (code "220") (name "GNDA") (class "Default")
      (node (ref "FB3") (pin "2") (pinfunction "2_2") (pintype "passive"))
      (node (ref "H1") (pin "58") (pinfunction "58_58") (pintype "passive"))
      (node (ref "U1") (pin "B2") (pinfunction "VSSA_B2") (pintype "power_in"))
    )
    (net (code "221") (name "Net-(D1-A)") (class "Default")
      (node (ref "D1") (pin "1") (pinfunction "A_1") (pintype "passive"))
      (node (ref "FB1") (pin "2") (pinfunction "2_2") (pintype "passive"))
    )
    (net (code "222") (name "Net-(D1-K)") (class "Default")
      (node (ref "C39") (pin "1") (pinfunction "1_1") (pintype "passive"))
      (node (ref "D1") (pin "2") (pinfunction "K_2") (pintype "passive"))
      (node (ref "U4") (pin "1") (pinfunction "Vin_1") (pintype "power_in"))
    )
    (net (code "223") (name "Net-(D2-CATHODE)") (class "Default")
      (node (ref "D2") (pin "2") (pinfunction "CATHODE_2") (pintype "passive"))
      (node (ref "R11") (pin "2") (pinfunction "2_2") (pintype "passive"))
    )
    (net (code "224") (name "Net-(U1E-USB0_RREF)") (class "Default")
      (node (ref "R10") (pin "2") (pinfunction "2_2") (pintype "passive"))
      (node (ref "U1") (pin "H1") (pinfunction "USB0_RREF_H1") (pintype "passive"))
    )
    (net (code "225") (name "Net-(U3-RBIAS)") (class "Default")
      (node (ref "R1") (pin "2") (pinfunction "2_2") (pintype "passive"))
      (node (ref "U3") (pin "19") (pinfunction "RBIAS_19") (pintype "passive"))
    )
    (net (code "226") (name "Net-(U3-VDD18)") (class "Default")
      (node (ref "C24") (pin "1") (pinfunction "1_1") (pintype "passive"))
      (node (ref "U3") (pin "23") (pinfunction "VDD18_23") (pintype "power_in"))
    )
    (net (code "227") (name "Net-(U3-VDD33)") (class "Default")
      (node (ref "C25") (pin "1") (pinfunction "1_1") (pintype "passive"))
      (node (ref "U3") (pin "15") (pinfunction "VDD33_15") (pintype "power_in"))
    )
    (net (code "228") (name "USB0_VBUS") (class "Default")
      (node (ref "FB1") (pin "1") (pinfunction "1_1") (pintype "passive"))
      (node (ref "H3") (pin "3") (pinfunction "3_3") (pintype "passive"))
      (node (ref "H3") (pin "4") (pinfunction "4_4") (pintype "passive"))
      (node (ref "J2") (pin "1") (pinfunction "VCC_1") (pintype "passive"))
      (node (ref "U1") (pin "F1") (pinfunction "USB0_VBUS_F1") (pintype "power_in"))
    )
    (net (code "229") (name "VBAT") (class "Default")
      (node (ref "C23") (pin "1") (pinfunction "1_1") (pintype "passive"))
      (node (ref "FB6") (pin "2") (pinfunction "2_2") (pintype "passive"))
      (node (ref "U3") (pin "16") (pinfunction "VBAT_16") (pintype "power_in"))
    )
    (net (code "230") (name "VDD") (class "Default")
      (node (ref "C27") (pin "1") (pinfunction "1_1") (pintype "passive"))
      (node (ref "C32") (pin "1") (pinfunction "1_1") (pintype "passive"))
      (node (ref "C33") (pin "1") (pinfunction "1_1") (pintype "passive"))
      (node (ref "FB5") (pin "1") (pinfunction "1_1") (pintype "passive"))
      (node (ref "U2") (pin "A9") (pinfunction "VDD_A9") (pintype "power_in"))
      (node (ref "U2") (pin "E7") (pinfunction "VDD_E7") (pintype "power_in"))
      (node (ref "U2") (pin "J9") (pinfunction "VDD_J9") (pintype "power_in"))
    )
    (net (code "231") (name "VDDA") (class "Default")
      (node (ref "C22") (pin "1") (pinfunction "1_1") (pintype "passive"))
      (node (ref "FB2") (pin "2") (pinfunction "2_2") (pintype "passive"))
      (node (ref "U1") (pin "B4") (pinfunction "VDDA_B4") (pintype "power_in"))
    )
    (net (code "232") (name "VDDIO") (class "Default")
      (node (ref "C26") (pin "1") (pinfunction "1_1") (pintype "passive"))
      (node (ref "FB7") (pin "2") (pinfunction "2_2") (pintype "passive"))
      (node (ref "U3") (pin "9") (pinfunction "VDDIO_9") (pintype "power_in"))
    )
    (net (code "233") (name "VDDQ") (class "Default")
      (node (ref "C28") (pin "1") (pinfunction "1_1") (pintype "passive"))
      (node (ref "C29") (pin "1") (pinfunction "1_1") (pintype "passive"))
      (node (ref "C30") (pin "1") (pinfunction "1_1") (pintype "passive"))
      (node (ref "C31") (pin "1") (pinfunction "1_1") (pintype "passive"))
      (node (ref "FB4") (pin "1") (pinfunction "1_1") (pintype "passive"))
      (node (ref "U2") (pin "A7") (pinfunction "VDDQ_A7") (pintype "power_in"))
      (node (ref "U2") (pin "B3") (pinfunction "VDDQ_B3") (pintype "power_in"))
      (node (ref "U2") (pin "C7") (pinfunction "VDDQ_C7") (pintype "power_in"))
      (node (ref "U2") (pin "D3") (pinfunction "VDDQ_D3") (pintype "power_in"))
    )
    (net (code "234") (name "unconnected-(H6-NC-Pad7)") (class "Default")
      (node (ref "H6") (pin "7") (pinfunction "NC_7") (pintype "passive+no_connect"))
    )
    (net (code "235") (name "unconnected-(S1-Pad1)") (class "Default")
      (node (ref "S1") (pin "1") (pinfunction "1_1") (pintype "passive+no_connect"))
    )
    (net (code "236") (name "unconnected-(U2A-NC-PadE2)") (class "Default")
      (node (ref "U2") (pin "E2") (pinfunction "NC_E2") (pintype "passive+no_connect"))
    )
  )
)
